# RT_SUPER_B1.net
KiCad netlist of a schematic drawn in Altium Designer
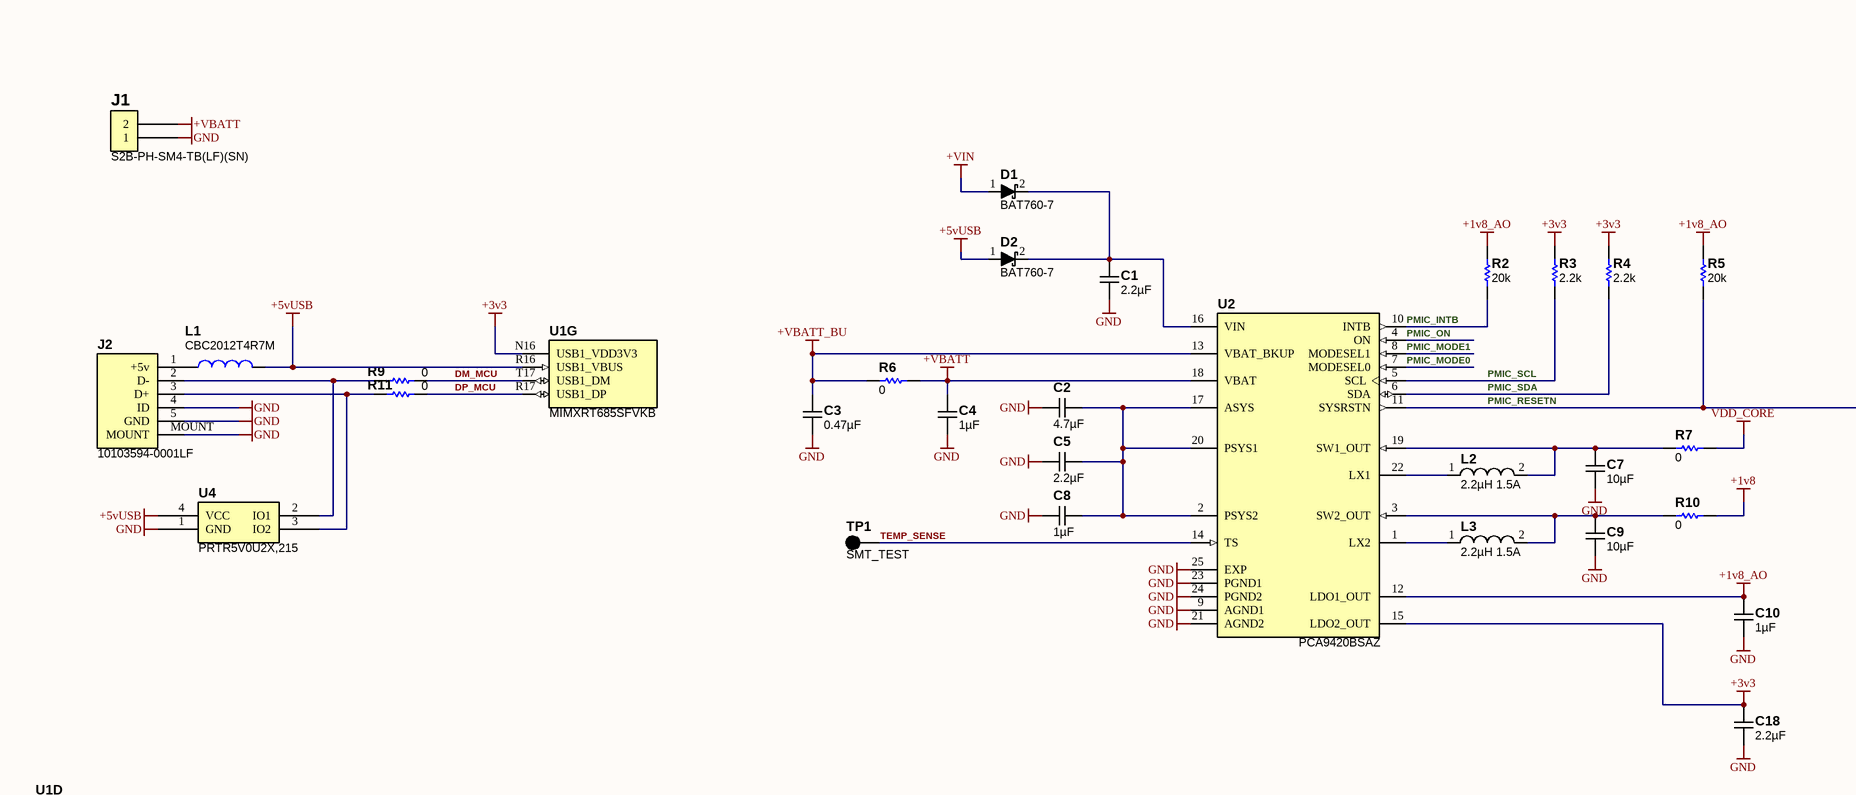
[diagram p0: RT_SUPER_B1.SchDoc, top left]
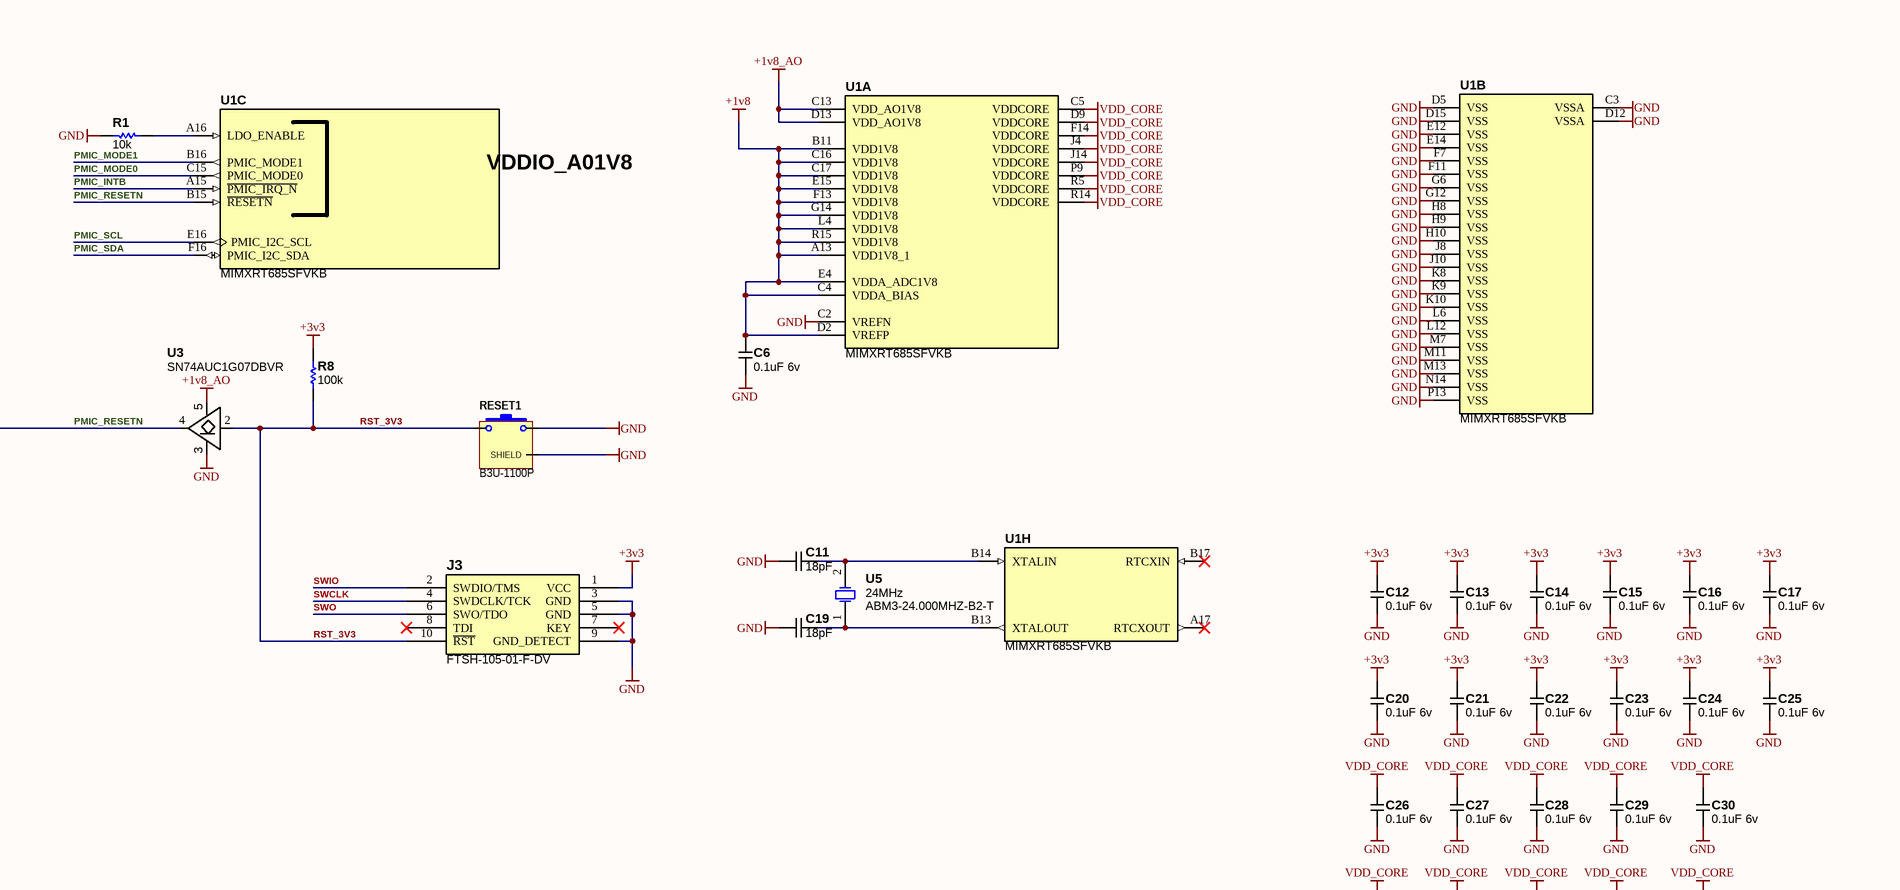
[diagram p1: RT_SUPER_B1.SchDoc, top right]
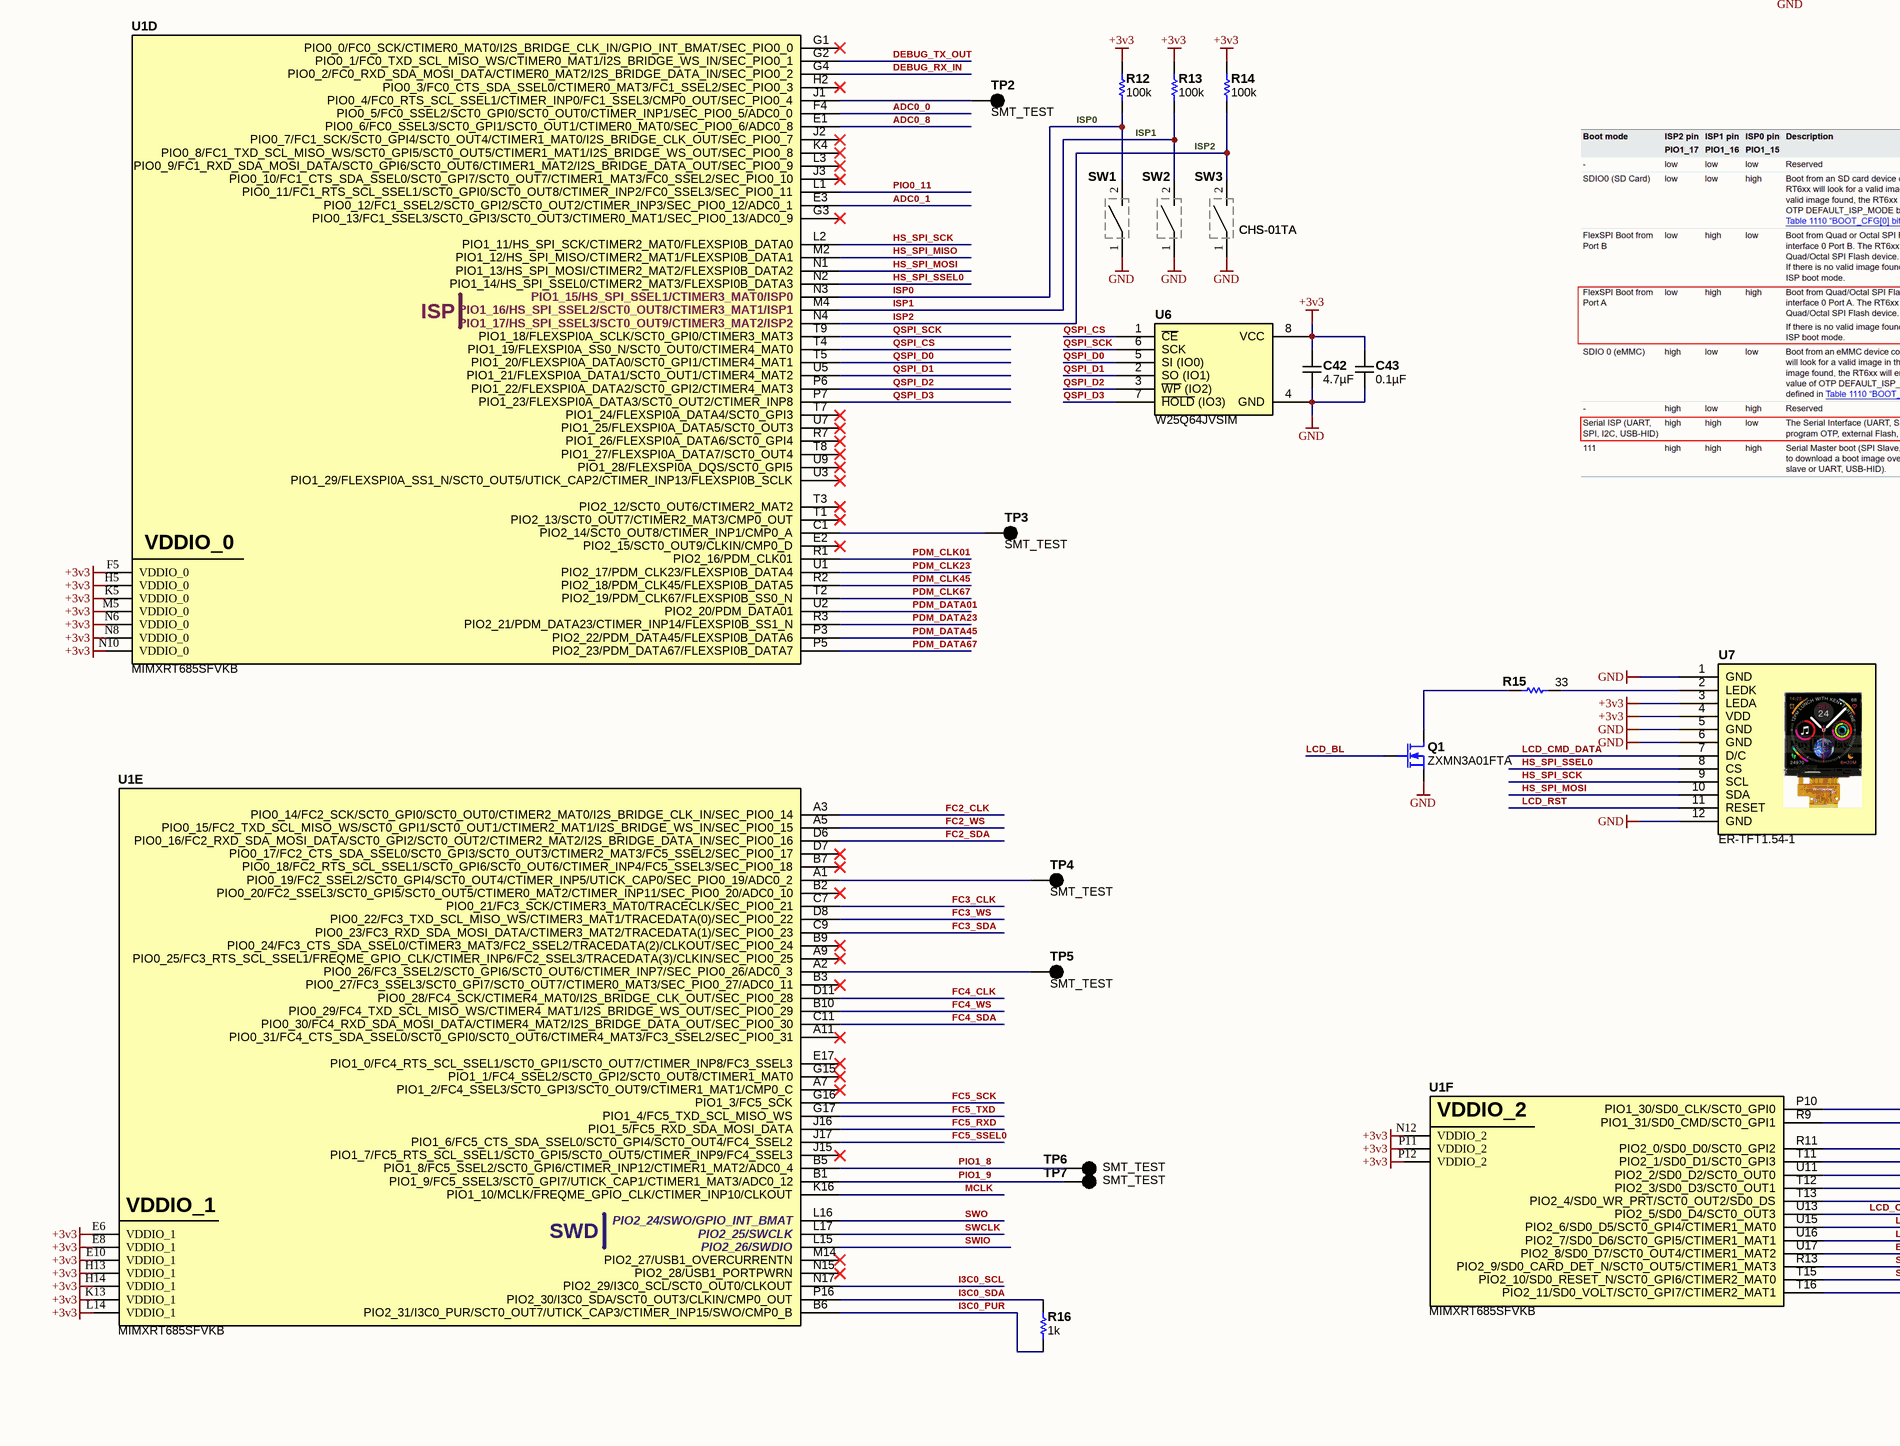
[diagram p2: RT_SUPER_B1.SchDoc, bottom left]
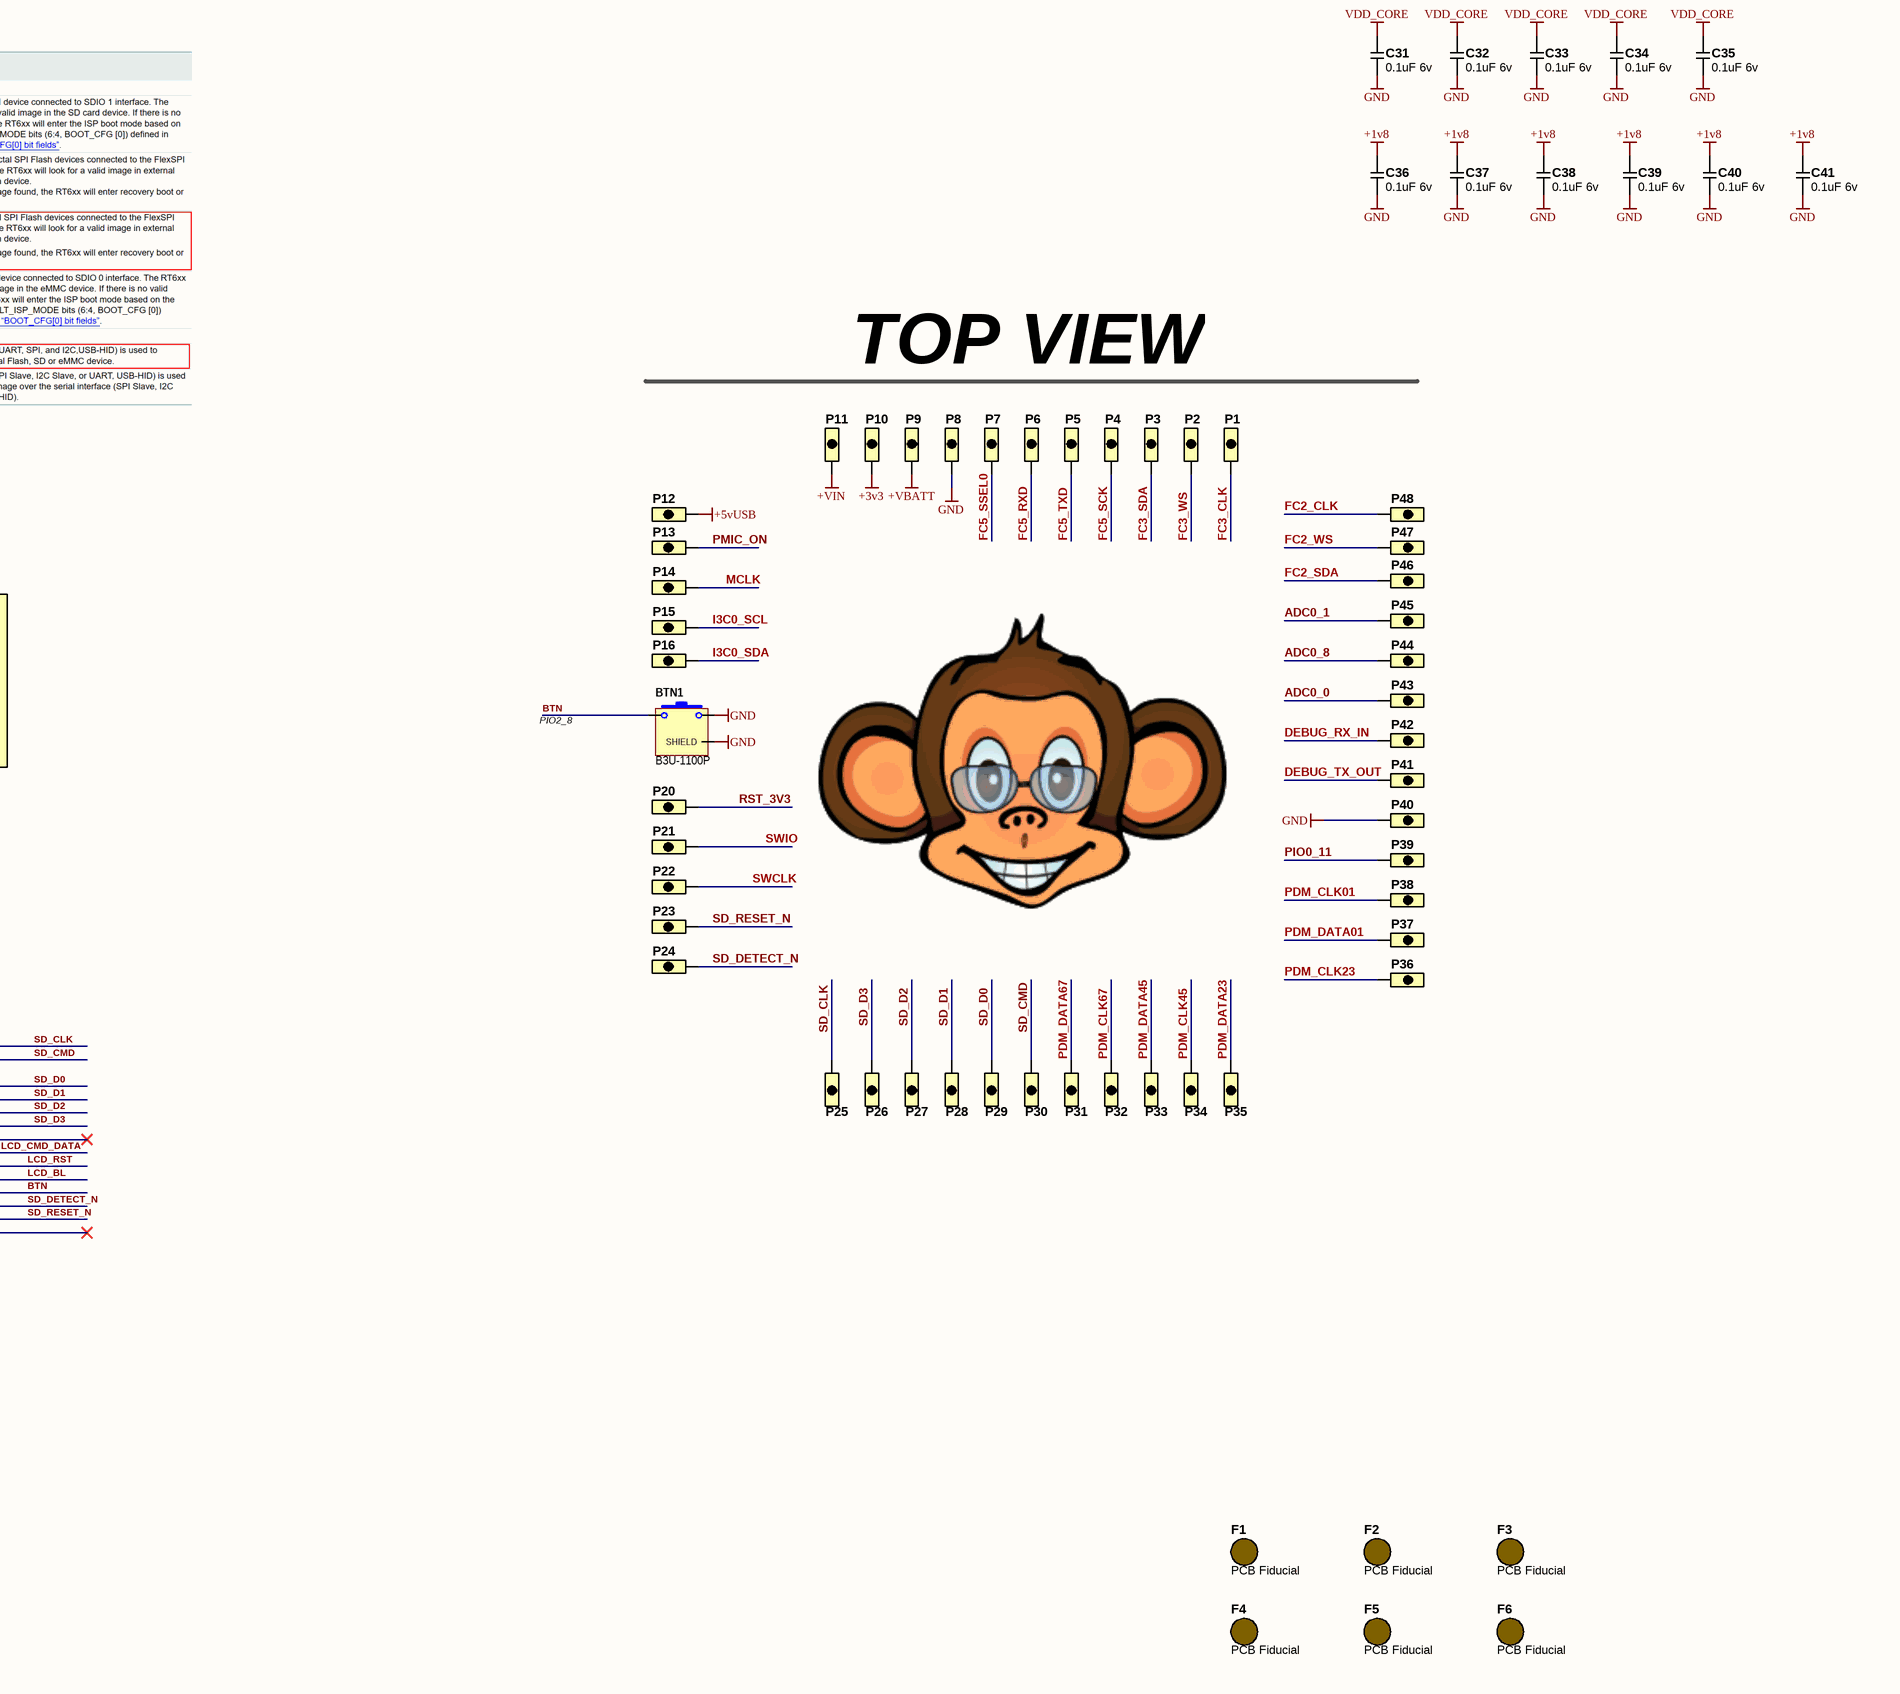
[diagram p3: RT_SUPER_B1.SchDoc, bottom right]

(export (version "E")
  (design (tool "Eeschema 10.0.6"))
  (components
    (comp (ref "BTN1")
      (value "B3U-1100P")
      (footprint "OMRON_B3U-1100P")
      (description "SWITCH TACTILE SPST-NO 0.05A 12V")
      (fields (field (name "MANUFACTURER") "Omron Electronics Inc-EMC Div"))
      (libsource (lib "Switches-N") (part "B3U-1100P"))
    )
    (comp (ref "C1")
      (value "2.2µF")
      (footprint "C0603_0.90MM_MD")
      (description "CAP CER 2.2UF 6.3V X7R 0603")
      (fields
        (field (name "MANUFACTURER PART NUMBER") "GCM188R70J225KE22D")
        (field (name "MANUFACTURER") "Murata Electronics")
      )
      (libsource (lib "Capacitors - Murata - AEC-Q200") (part "C_2P_NP"))
    )
    (comp (ref "C2")
      (value "4.7µF")
      (footprint "C0603_1.00MM_MD")
      (description "CAP CER 4.7UF 6.3V X7S 0603")
      (fields
        (field (name "MANUFACTURER PART NUMBER") "GCJ188C70J475KE02D")
        (field (name "MANUFACTURER") "Murata Electronics")
      )
      (libsource (lib "Capacitors - Murata - AEC-Q200") (part "C_2P_NP"))
    )
    (comp (ref "C3")
      (value "0.47µF")
      (footprint "C0402_0.55MM_HD")
      (description "CAP CER 0.47UF 25V X5R 0402")
      (fields
        (field (name "MANUFACTURER PART NUMBER") "GRT155R61E474KE01D")
        (field (name "MANUFACTURER") "Murata Electronics")
      )
      (libsource (lib "Capacitors - Murata - AEC-Q200") (part "C_2P_NP"))
    )
    (comp (ref "C4")
      (value "1µF")
      (footprint "C0402_0.55MM_HD")
      (description "CAP CER 1UF 10V X7S 0402")
      (fields
        (field (name "MANUFACTURER PART NUMBER") "GCM155C71A105KE38D")
        (field (name "MANUFACTURER") "Murata Electronics")
      )
      (libsource (lib "Capacitors - Murata - AEC-Q200") (part "C_2P_NP"))
    )
    (comp (ref "C5")
      (value "2.2µF")
      (footprint "C0603_0.90MM_MD")
      (description "CAP CER 2.2UF 6.3V X7R 0603")
      (fields
        (field (name "MANUFACTURER PART NUMBER") "GCM188R70J225KE22D")
        (field (name "MANUFACTURER") "Murata Electronics")
      )
      (libsource (lib "Capacitors - Murata - AEC-Q200") (part "C_2P_NP"))
    )
    (comp (ref "C6")
      (value "0.1uF 6v")
      (footprint "C0201_PERFECT")
      (description "Cap Ceramic 0.1uF 6.3VDC X5R 10% SMD 0201 Paper T/R")
      (fields
        (field (name "MANUFACTURER PART NUMBER") "CC0201KRX5R5BB104")
        (field (name "MANUFACTURER") "Yageo")
      )
      (libsource (lib "eCapacitors") (part "CC0201KRX5R5BB104"))
    )
    (comp (ref "C7")
      (value "10µF")
      (footprint "C0603_0.90MM_MD")
      (description "CAP CER 10UF 10V X5R 0603")
      (fields
        (field (name "MANUFACTURER PART NUMBER") "GRT188R61A106ME13D")
        (field (name "MANUFACTURER") "Murata Electronics")
      )
      (libsource (lib "Capacitors - Murata - AEC-Q200") (part "C_2P_NP"))
    )
    (comp (ref "C8")
      (value "1µF")
      (footprint "C0402_0.55MM_HD")
      (description "CAP CER 1UF 10V X7S 0402")
      (fields
        (field (name "MANUFACTURER PART NUMBER") "GCM155C71A105KE38D")
        (field (name "MANUFACTURER") "Murata Electronics")
      )
      (libsource (lib "Capacitors - Murata - AEC-Q200") (part "C_2P_NP"))
    )
    (comp (ref "C9")
      (value "10µF")
      (footprint "C0603_0.90MM_MD")
      (description "CAP CER 10UF 10V X5R 0603")
      (fields
        (field (name "MANUFACTURER PART NUMBER") "GRT188R61A106ME13D")
        (field (name "MANUFACTURER") "Murata Electronics")
      )
      (libsource (lib "Capacitors - Murata - AEC-Q200") (part "C_2P_NP"))
    )
    (comp (ref "C10")
      (value "1µF")
      (footprint "C0402_0.55MM_HD")
      (description "CAP CER 1UF 10V X7S 0402")
      (fields
        (field (name "MANUFACTURER PART NUMBER") "GCM155C71A105KE38D")
        (field (name "MANUFACTURER") "Murata Electronics")
      )
      (libsource (lib "Capacitors - Murata - AEC-Q200") (part "C_2P_NP"))
    )
    (comp (ref "C11")
      (value "18pF")
      (footprint "C0402_0.55MM_HD")
      (description "CAP CER 18PF 50V C0G 0402")
      (fields
        (field (name "MANUFACTURER PART NUMBER") "CGA2B2C0G1H180J050BA")
        (field (name "MANUFACTURER") "TDK Corporation")
      )
      (libsource (lib "Capacitors - TDK- AEC-Q200") (part "C_2P_NP"))
    )
    (comp (ref "C12")
      (value "0.1uF 6v")
      (footprint "C0201_PERFECT")
      (description "Cap Ceramic 0.1uF 6.3VDC X5R 10% SMD 0201 Paper T/R")
      (fields
        (field (name "MANUFACTURER PART NUMBER") "CC0201KRX5R5BB104")
        (field (name "MANUFACTURER") "Yageo")
      )
      (libsource (lib "eCapacitors") (part "CC0201KRX5R5BB104"))
    )
    (comp (ref "C13")
      (value "0.1uF 6v")
      (footprint "C0201_PERFECT")
      (description "Cap Ceramic 0.1uF 6.3VDC X5R 10% SMD 0201 Paper T/R")
      (fields
        (field (name "MANUFACTURER PART NUMBER") "CC0201KRX5R5BB104")
        (field (name "MANUFACTURER") "Yageo")
      )
      (libsource (lib "eCapacitors") (part "CC0201KRX5R5BB104"))
    )
    (comp (ref "C14")
      (value "0.1uF 6v")
      (footprint "C0201_PERFECT")
      (description "Cap Ceramic 0.1uF 6.3VDC X5R 10% SMD 0201 Paper T/R")
      (fields
        (field (name "MANUFACTURER PART NUMBER") "CC0201KRX5R5BB104")
        (field (name "MANUFACTURER") "Yageo")
      )
      (libsource (lib "eCapacitors") (part "CC0201KRX5R5BB104"))
    )
    (comp (ref "C15")
      (value "0.1uF 6v")
      (footprint "C0201_PERFECT")
      (description "Cap Ceramic 0.1uF 6.3VDC X5R 10% SMD 0201 Paper T/R")
      (fields
        (field (name "MANUFACTURER PART NUMBER") "CC0201KRX5R5BB104")
        (field (name "MANUFACTURER") "Yageo")
      )
      (libsource (lib "eCapacitors") (part "CC0201KRX5R5BB104"))
    )
    (comp (ref "C16")
      (value "0.1uF 6v")
      (footprint "C0201_PERFECT")
      (description "Cap Ceramic 0.1uF 6.3VDC X5R 10% SMD 0201 Paper T/R")
      (fields
        (field (name "MANUFACTURER PART NUMBER") "CC0201KRX5R5BB104")
        (field (name "MANUFACTURER") "Yageo")
      )
      (libsource (lib "eCapacitors") (part "CC0201KRX5R5BB104"))
    )
    (comp (ref "C17")
      (value "0.1uF 6v")
      (footprint "C0201_PERFECT")
      (description "Cap Ceramic 0.1uF 6.3VDC X5R 10% SMD 0201 Paper T/R")
      (fields
        (field (name "MANUFACTURER PART NUMBER") "CC0201KRX5R5BB104")
        (field (name "MANUFACTURER") "Yageo")
      )
      (libsource (lib "eCapacitors") (part "CC0201KRX5R5BB104"))
    )
    (comp (ref "C18")
      (value "2.2µF")
      (footprint "C0603_0.90MM_MD")
      (description "CAP CER 2.2UF 6.3V X7R 0603")
      (fields
        (field (name "MANUFACTURER PART NUMBER") "GCM188R70J225KE22D")
        (field (name "MANUFACTURER") "Murata Electronics")
      )
      (libsource (lib "Capacitors - Murata - AEC-Q200") (part "C_2P_NP"))
    )
    (comp (ref "C19")
      (value "18pF")
      (footprint "C0402_0.55MM_HD")
      (description "CAP CER 18PF 50V C0G 0402")
      (fields
        (field (name "MANUFACTURER PART NUMBER") "CGA2B2C0G1H180J050BA")
        (field (name "MANUFACTURER") "TDK Corporation")
      )
      (libsource (lib "Capacitors - TDK- AEC-Q200") (part "C_2P_NP"))
    )
    (comp (ref "C20")
      (value "0.1uF 6v")
      (footprint "C0201_PERFECT")
      (description "Cap Ceramic 0.1uF 6.3VDC X5R 10% SMD 0201 Paper T/R")
      (fields
        (field (name "MANUFACTURER PART NUMBER") "CC0201KRX5R5BB104")
        (field (name "MANUFACTURER") "Yageo")
      )
      (libsource (lib "eCapacitors") (part "CC0201KRX5R5BB104"))
    )
    (comp (ref "C21")
      (value "0.1uF 6v")
      (footprint "C0201_PERFECT")
      (description "Cap Ceramic 0.1uF 6.3VDC X5R 10% SMD 0201 Paper T/R")
      (fields
        (field (name "MANUFACTURER PART NUMBER") "CC0201KRX5R5BB104")
        (field (name "MANUFACTURER") "Yageo")
      )
      (libsource (lib "eCapacitors") (part "CC0201KRX5R5BB104"))
    )
    (comp (ref "C22")
      (value "0.1uF 6v")
      (footprint "C0201_PERFECT")
      (description "Cap Ceramic 0.1uF 6.3VDC X5R 10% SMD 0201 Paper T/R")
      (fields
        (field (name "MANUFACTURER PART NUMBER") "CC0201KRX5R5BB104")
        (field (name "MANUFACTURER") "Yageo")
      )
      (libsource (lib "eCapacitors") (part "CC0201KRX5R5BB104"))
    )
    (comp (ref "C23")
      (value "0.1uF 6v")
      (footprint "C0201_PERFECT")
      (description "Cap Ceramic 0.1uF 6.3VDC X5R 10% SMD 0201 Paper T/R")
      (fields
        (field (name "MANUFACTURER PART NUMBER") "CC0201KRX5R5BB104")
        (field (name "MANUFACTURER") "Yageo")
      )
      (libsource (lib "eCapacitors") (part "CC0201KRX5R5BB104"))
    )
    (comp (ref "C24")
      (value "0.1uF 6v")
      (footprint "C0201_PERFECT")
      (description "Cap Ceramic 0.1uF 6.3VDC X5R 10% SMD 0201 Paper T/R")
      (fields
        (field (name "MANUFACTURER PART NUMBER") "CC0201KRX5R5BB104")
        (field (name "MANUFACTURER") "Yageo")
      )
      (libsource (lib "eCapacitors") (part "CC0201KRX5R5BB104"))
    )
    (comp (ref "C25")
      (value "0.1uF 6v")
      (footprint "C0201_PERFECT")
      (description "Cap Ceramic 0.1uF 6.3VDC X5R 10% SMD 0201 Paper T/R")
      (fields
        (field (name "MANUFACTURER PART NUMBER") "CC0201KRX5R5BB104")
        (field (name "MANUFACTURER") "Yageo")
      )
      (libsource (lib "eCapacitors") (part "CC0201KRX5R5BB104"))
    )
    (comp (ref "C26")
      (value "0.1uF 6v")
      (footprint "C0201_PERFECT")
      (description "Cap Ceramic 0.1uF 6.3VDC X5R 10% SMD 0201 Paper T/R")
      (fields
        (field (name "MANUFACTURER PART NUMBER") "CC0201KRX5R5BB104")
        (field (name "MANUFACTURER") "Yageo")
      )
      (libsource (lib "eCapacitors") (part "CC0201KRX5R5BB104"))
    )
    (comp (ref "C27")
      (value "0.1uF 6v")
      (footprint "C0201_PERFECT")
      (description "Cap Ceramic 0.1uF 6.3VDC X5R 10% SMD 0201 Paper T/R")
      (fields
        (field (name "MANUFACTURER PART NUMBER") "CC0201KRX5R5BB104")
        (field (name "MANUFACTURER") "Yageo")
      )
      (libsource (lib "eCapacitors") (part "CC0201KRX5R5BB104"))
    )
    (comp (ref "C28")
      (value "0.1uF 6v")
      (footprint "C0201_PERFECT")
      (description "Cap Ceramic 0.1uF 6.3VDC X5R 10% SMD 0201 Paper T/R")
      (fields
        (field (name "MANUFACTURER PART NUMBER") "CC0201KRX5R5BB104")
        (field (name "MANUFACTURER") "Yageo")
      )
      (libsource (lib "eCapacitors") (part "CC0201KRX5R5BB104"))
    )
    (comp (ref "C29")
      (value "0.1uF 6v")
      (footprint "C0201_PERFECT")
      (description "Cap Ceramic 0.1uF 6.3VDC X5R 10% SMD 0201 Paper T/R")
      (fields
        (field (name "MANUFACTURER PART NUMBER") "CC0201KRX5R5BB104")
        (field (name "MANUFACTURER") "Yageo")
      )
      (libsource (lib "eCapacitors") (part "CC0201KRX5R5BB104"))
    )
    (comp (ref "C30")
      (value "0.1uF 6v")
      (footprint "C0201_PERFECT")
      (description "Cap Ceramic 0.1uF 6.3VDC X5R 10% SMD 0201 Paper T/R")
      (fields
        (field (name "MANUFACTURER PART NUMBER") "CC0201KRX5R5BB104")
        (field (name "MANUFACTURER") "Yageo")
      )
      (libsource (lib "eCapacitors") (part "CC0201KRX5R5BB104"))
    )
    (comp (ref "C31")
      (value "0.1uF 6v")
      (footprint "C0201_PERFECT")
      (description "Cap Ceramic 0.1uF 6.3VDC X5R 10% SMD 0201 Paper T/R")
      (fields
        (field (name "MANUFACTURER PART NUMBER") "CC0201KRX5R5BB104")
        (field (name "MANUFACTURER") "Yageo")
      )
      (libsource (lib "eCapacitors") (part "CC0201KRX5R5BB104"))
    )
    (comp (ref "C32")
      (value "0.1uF 6v")
      (footprint "C0201_PERFECT")
      (description "Cap Ceramic 0.1uF 6.3VDC X5R 10% SMD 0201 Paper T/R")
      (fields
        (field (name "MANUFACTURER PART NUMBER") "CC0201KRX5R5BB104")
        (field (name "MANUFACTURER") "Yageo")
      )
      (libsource (lib "eCapacitors") (part "CC0201KRX5R5BB104"))
    )
    (comp (ref "C33")
      (value "0.1uF 6v")
      (footprint "C0201_PERFECT")
      (description "Cap Ceramic 0.1uF 6.3VDC X5R 10% SMD 0201 Paper T/R")
      (fields
        (field (name "MANUFACTURER PART NUMBER") "CC0201KRX5R5BB104")
        (field (name "MANUFACTURER") "Yageo")
      )
      (libsource (lib "eCapacitors") (part "CC0201KRX5R5BB104"))
    )
    (comp (ref "C34")
      (value "0.1uF 6v")
      (footprint "C0201_PERFECT")
      (description "Cap Ceramic 0.1uF 6.3VDC X5R 10% SMD 0201 Paper T/R")
      (fields
        (field (name "MANUFACTURER PART NUMBER") "CC0201KRX5R5BB104")
        (field (name "MANUFACTURER") "Yageo")
      )
      (libsource (lib "eCapacitors") (part "CC0201KRX5R5BB104"))
    )
    (comp (ref "C35")
      (value "0.1uF 6v")
      (footprint "C0201_PERFECT")
      (description "Cap Ceramic 0.1uF 6.3VDC X5R 10% SMD 0201 Paper T/R")
      (fields
        (field (name "MANUFACTURER PART NUMBER") "CC0201KRX5R5BB104")
        (field (name "MANUFACTURER") "Yageo")
      )
      (libsource (lib "eCapacitors") (part "CC0201KRX5R5BB104"))
    )
    (comp (ref "C36")
      (value "0.1uF 6v")
      (footprint "C0201_PERFECT")
      (description "Cap Ceramic 0.1uF 6.3VDC X5R 10% SMD 0201 Paper T/R")
      (fields
        (field (name "MANUFACTURER PART NUMBER") "CC0201KRX5R5BB104")
        (field (name "MANUFACTURER") "Yageo")
      )
      (libsource (lib "eCapacitors") (part "CC0201KRX5R5BB104"))
    )
    (comp (ref "C37")
      (value "0.1uF 6v")
      (footprint "C0201_PERFECT")
      (description "Cap Ceramic 0.1uF 6.3VDC X5R 10% SMD 0201 Paper T/R")
      (fields
        (field (name "MANUFACTURER PART NUMBER") "CC0201KRX5R5BB104")
        (field (name "MANUFACTURER") "Yageo")
      )
      (libsource (lib "eCapacitors") (part "CC0201KRX5R5BB104"))
    )
    (comp (ref "C38")
      (value "0.1uF 6v")
      (footprint "C0201_PERFECT")
      (description "Cap Ceramic 0.1uF 6.3VDC X5R 10% SMD 0201 Paper T/R")
      (fields
        (field (name "MANUFACTURER PART NUMBER") "CC0201KRX5R5BB104")
        (field (name "MANUFACTURER") "Yageo")
      )
      (libsource (lib "eCapacitors") (part "CC0201KRX5R5BB104"))
    )
    (comp (ref "C39")
      (value "0.1uF 6v")
      (footprint "C0201_PERFECT")
      (description "Cap Ceramic 0.1uF 6.3VDC X5R 10% SMD 0201 Paper T/R")
      (fields
        (field (name "MANUFACTURER PART NUMBER") "CC0201KRX5R5BB104")
        (field (name "MANUFACTURER") "Yageo")
      )
      (libsource (lib "eCapacitors") (part "CC0201KRX5R5BB104"))
    )
    (comp (ref "C40")
      (value "0.1uF 6v")
      (footprint "C0201_PERFECT")
      (description "Cap Ceramic 0.1uF 6.3VDC X5R 10% SMD 0201 Paper T/R")
      (fields
        (field (name "MANUFACTURER PART NUMBER") "CC0201KRX5R5BB104")
        (field (name "MANUFACTURER") "Yageo")
      )
      (libsource (lib "eCapacitors") (part "CC0201KRX5R5BB104"))
    )
    (comp (ref "C41")
      (value "0.1uF 6v")
      (footprint "C0201_PERFECT")
      (description "Cap Ceramic 0.1uF 6.3VDC X5R 10% SMD 0201 Paper T/R")
      (fields
        (field (name "MANUFACTURER PART NUMBER") "CC0201KRX5R5BB104")
        (field (name "MANUFACTURER") "Yageo")
      )
      (libsource (lib "eCapacitors") (part "CC0201KRX5R5BB104"))
    )
    (comp (ref "C42")
      (value "4.7µF")
      (footprint "C0805_1.45MM_MD")
      (description "CAP CER 4.7UF 10V X7R 0805")
      (fields
        (field (name "MANUFACTURER PART NUMBER") "CGA4J3X7R1A475K125AB")
        (field (name "MANUFACTURER") "TDK Corporation")
      )
      (libsource (lib "Capacitors - TDK- AEC-Q200") (part "C_2P_NP"))
    )
    (comp (ref "C43")
      (value "0.1µF")
      (footprint "C0402_0.55MM_MD")
      (description "CAP CER 0.1UF 16V X7R 0402")
      (fields
        (field (name "MANUFACTURER PART NUMBER") "CGA2B1X7R1C104K050BC")
        (field (name "MANUFACTURER") "TDK Corporation")
      )
      (libsource (lib "Capacitors - TDK- AEC-Q200") (part "C_2P_NP"))
    )
    (comp (ref "D1")
      (value "BAT760-7")
      (footprint "D_SOD-323_P")
      (description "DIODE SCHOTTKY 30V 1A SOD323")
      (fields (field (name "MANUFACTURER") "Diodes Inc"))
      (libsource (lib "Diodes") (part "DS_1A_2C"))
    )
    (comp (ref "D2")
      (value "BAT760-7")
      (footprint "D_SOD-323_P")
      (description "DIODE SCHOTTKY 30V 1A SOD323")
      (fields (field (name "MANUFACTURER") "Diodes Inc"))
      (libsource (lib "Diodes") (part "DS_1A_2C"))
    )
    (comp (ref "F1")
      (value "PCB Fiducial")
      (footprint "Fiducial 1mm - 2mm")
      (libsource (lib "eFiducial") (part "Fiducial"))
    )
    (comp (ref "F2")
      (value "PCB Fiducial")
      (footprint "Fiducial 1mm - 2mm")
      (libsource (lib "eFiducial") (part "Fiducial"))
    )
    (comp (ref "F3")
      (value "PCB Fiducial")
      (footprint "Fiducial 1mm - 2mm")
      (libsource (lib "eFiducial") (part "Fiducial"))
    )
    (comp (ref "F4")
      (value "PCB Fiducial")
      (footprint "Fiducial 1mm - 2mm")
      (libsource (lib "eFiducial") (part "Fiducial"))
    )
    (comp (ref "F5")
      (value "PCB Fiducial")
      (footprint "Fiducial 1mm - 2mm")
      (libsource (lib "eFiducial") (part "Fiducial"))
    )
    (comp (ref "F6")
      (value "PCB Fiducial")
      (footprint "Fiducial 1mm - 2mm")
      (libsource (lib "eFiducial") (part "Fiducial"))
    )
    (comp (ref "J1")
      (value "S2B-PH-SM4-TB(LF)(SN)")
      (footprint "S2B-PH-SM4-TB(LF)(SN)")
      (description "CONN HEADER PH SIDE 2POS 2MM SMD")
      (fields (field (name "MANUFACTURER") "JST Sales America Inc"))
      (libsource (lib "eConnector_JST_PH") (part "S2B-PH-SM4-TB(LF)(SN)"))
    )
    (comp (ref "J2")
      (value "10103594-0001LF")
      (footprint "10103594-0001LF")
      (description "CONN RCPT STD MICRO USB TYPE B")
      (fields (field (name "MANUFACTURER") "FCI"))
      (libsource (lib "eConnector_USB") (part "10103594-0001LF"))
    )
    (comp (ref "J3")
      (value "FTSH-105-01-F-DV")
      (footprint "FTSH-105-01-F-DV-K-A")
      (description "SAMTEC - FTSH-105-01-F-DV - .050 X .050")
      (fields (field (name "MANUFACTURER") "SAMTEC"))
      (libsource (lib "eConnector") (part "CORTEX-DEBUG"))
    )
    (comp (ref "L1")
      (value "CBC2012T4R7M")
      (footprint "C0805_1.45MM_MD")
      (description "FIXED IND 4.7UH 520MA 650 MOHM")
      (fields (field (name "MANUFACTURER") "Taiyo Yuden") (field (name "TOLERANCE") "20%"))
      (libsource (lib "eInductor") (part "CBC2012T4R7M"))
    )
    (comp (ref "L2")
      (value "2.2µH 1.5A")
      (footprint "L_NRH3012")
      (description "Inductor 2.2µH 1.5A")
      (fields
        (field (name "MANUFACTURER PART NUMBER") "NRH3012T2R2MN")
        (field (name "MANUFACTURER") "Taiyo Yuden")
      )
      (libsource (lib "Inductors") (part "L_2P"))
    )
    (comp (ref "L3")
      (value "2.2µH 1.5A")
      (footprint "L_NRH3012")
      (description "Inductor 2.2µH 1.5A")
      (fields
        (field (name "MANUFACTURER PART NUMBER") "NRH3012T2R2MN")
        (field (name "MANUFACTURER") "Taiyo Yuden")
      )
      (libsource (lib "Inductors") (part "L_2P"))
    )
    (comp (ref "P1")
      (value "~")
      (footprint "CASTELLATED")
      (libsource (lib "eConnector") (part "CASTELLATED"))
    )
    (comp (ref "P2")
      (value "~")
      (footprint "CASTELLATED")
      (libsource (lib "eConnector") (part "CASTELLATED"))
    )
    (comp (ref "P3")
      (value "~")
      (footprint "CASTELLATED")
      (libsource (lib "eConnector") (part "CASTELLATED"))
    )
    (comp (ref "P4")
      (value "~")
      (footprint "CASTELLATED")
      (libsource (lib "eConnector") (part "CASTELLATED"))
    )
    (comp (ref "P5")
      (value "~")
      (footprint "CASTELLATED")
      (libsource (lib "eConnector") (part "CASTELLATED"))
    )
    (comp (ref "P6")
      (value "~")
      (footprint "CASTELLATED")
      (libsource (lib "eConnector") (part "CASTELLATED"))
    )
    (comp (ref "P7")
      (value "~")
      (footprint "CASTELLATED")
      (libsource (lib "eConnector") (part "CASTELLATED"))
    )
    (comp (ref "P8")
      (value "~")
      (footprint "CASTELLATED")
      (libsource (lib "eConnector") (part "CASTELLATED"))
    )
    (comp (ref "P9")
      (value "~")
      (footprint "CASTELLATED")
      (libsource (lib "eConnector") (part "CASTELLATED"))
    )
    (comp (ref "P10")
      (value "~")
      (footprint "CASTELLATED")
      (libsource (lib "eConnector") (part "CASTELLATED"))
    )
    (comp (ref "P11")
      (value "~")
      (footprint "CASTELLATED")
      (libsource (lib "eConnector") (part "CASTELLATED"))
    )
    (comp (ref "P12") (value "~") (footprint "CASTELLATED") (libsource (lib "") (part "CASTELLATED_1")))
    (comp (ref "P13") (value "~") (footprint "CASTELLATED") (libsource (lib "") (part "CASTELLATED_2")))
    (comp (ref "P14") (value "~") (footprint "CASTELLATED") (libsource (lib "") (part "CASTELLATED_2")))
    (comp (ref "P15") (value "~") (footprint "CASTELLATED") (libsource (lib "") (part "CASTELLATED_2")))
    (comp (ref "P16") (value "~") (footprint "CASTELLATED") (libsource (lib "") (part "CASTELLATED_2")))
    (comp (ref "P20") (value "~") (footprint "CASTELLATED") (libsource (lib "") (part "CASTELLATED_2")))
    (comp (ref "P21") (value "~") (footprint "CASTELLATED") (libsource (lib "") (part "CASTELLATED_2")))
    (comp (ref "P22") (value "~") (footprint "CASTELLATED") (libsource (lib "") (part "CASTELLATED_2")))
    (comp (ref "P23") (value "~") (footprint "CASTELLATED") (libsource (lib "") (part "CASTELLATED_2")))
    (comp (ref "P24") (value "~") (footprint "CASTELLATED") (libsource (lib "") (part "CASTELLATED_1")))
    (comp (ref "P25") (value "~") (footprint "CASTELLATED") (libsource (lib "") (part "CASTELLATED_1")))
    (comp (ref "P26") (value "~") (footprint "CASTELLATED") (libsource (lib "") (part "CASTELLATED_1")))
    (comp (ref "P27") (value "~") (footprint "CASTELLATED") (libsource (lib "") (part "CASTELLATED_1")))
    (comp (ref "P28") (value "~") (footprint "CASTELLATED") (libsource (lib "") (part "CASTELLATED_1")))
    (comp (ref "P29") (value "~") (footprint "CASTELLATED") (libsource (lib "") (part "CASTELLATED_1")))
    (comp (ref "P30") (value "~") (footprint "CASTELLATED") (libsource (lib "") (part "CASTELLATED_1")))
    (comp (ref "P31") (value "~") (footprint "CASTELLATED") (libsource (lib "") (part "CASTELLATED_1")))
    (comp (ref "P32") (value "~") (footprint "CASTELLATED") (libsource (lib "") (part "CASTELLATED_1")))
    (comp (ref "P33") (value "~") (footprint "CASTELLATED") (libsource (lib "") (part "CASTELLATED_1")))
    (comp (ref "P34") (value "~") (footprint "CASTELLATED") (libsource (lib "") (part "CASTELLATED_1")))
    (comp (ref "P35") (value "~") (footprint "CASTELLATED") (libsource (lib "") (part "CASTELLATED_1")))
    (comp (ref "P36")
      (value "~")
      (footprint "CASTELLATED")
      (libsource (lib "eConnector") (part "CASTELLATED"))
    )
    (comp (ref "P37")
      (value "~")
      (footprint "CASTELLATED")
      (libsource (lib "eConnector") (part "CASTELLATED"))
    )
    (comp (ref "P38")
      (value "~")
      (footprint "CASTELLATED")
      (libsource (lib "eConnector") (part "CASTELLATED"))
    )
    (comp (ref "P39")
      (value "~")
      (footprint "CASTELLATED")
      (libsource (lib "eConnector") (part "CASTELLATED"))
    )
    (comp (ref "P40")
      (value "~")
      (footprint "CASTELLATED")
      (libsource (lib "eConnector") (part "CASTELLATED"))
    )
    (comp (ref "P41")
      (value "~")
      (footprint "CASTELLATED")
      (libsource (lib "eConnector") (part "CASTELLATED"))
    )
    (comp (ref "P42")
      (value "~")
      (footprint "CASTELLATED")
      (libsource (lib "eConnector") (part "CASTELLATED"))
    )
    (comp (ref "P43")
      (value "~")
      (footprint "CASTELLATED")
      (libsource (lib "eConnector") (part "CASTELLATED"))
    )
    (comp (ref "P44")
      (value "~")
      (footprint "CASTELLATED")
      (libsource (lib "eConnector") (part "CASTELLATED"))
    )
    (comp (ref "P45")
      (value "~")
      (footprint "CASTELLATED")
      (libsource (lib "eConnector") (part "CASTELLATED"))
    )
    (comp (ref "P46")
      (value "~")
      (footprint "CASTELLATED")
      (libsource (lib "eConnector") (part "CASTELLATED"))
    )
    (comp (ref "P47")
      (value "~")
      (footprint "CASTELLATED")
      (libsource (lib "eConnector") (part "CASTELLATED"))
    )
    (comp (ref "P48")
      (value "~")
      (footprint "CASTELLATED")
      (libsource (lib "eConnector") (part "CASTELLATED"))
    )
    (comp (ref "Q1")
      (value "ZXMN3A01FTA")
      (footprint "SOT-23")
      (description "MOSFET N-CH 30V 1.8A SOT23-3")
      (fields (field (name "MANUFACTURER") "Diodes/Zetex"))
      (libsource (lib "eTransistor") (part "ZXMN3A01FTA"))
    )
    (comp (ref "R1")
      (value "10k")
      (footprint "R0402_0.40MM_HD")
      (description "RES 10K OHM 1/10W 1% 0402 SMD")
      (fields
        (field (name "MANUFACTURER PART NUMBER") "ERJ-2RKF1002X")
        (field (name "MANUFACTURER") "Panasonic Electronic Components")
      )
      (libsource (lib "Resistors - Panasonic - AEC-Q200") (part "R_2P"))
    )
    (comp (ref "R2")
      (value "20k")
      (footprint "R0402_0.40MM_HD")
      (description "RES 20K OHM 1/10W 1% 0402 SMD")
      (fields
        (field (name "MANUFACTURER PART NUMBER") "ERJ-2RKF2002X")
        (field (name "MANUFACTURER") "Panasonic Electronic Components")
      )
      (libsource (lib "Resistors - Panasonic - AEC-Q200") (part "R_2P"))
    )
    (comp (ref "R3")
      (value "2.2k")
      (footprint "R0402_0.40MM_HD")
      (description "RES 2.2K OHM 1/10W 1% 0402 SMD")
      (fields
        (field (name "MANUFACTURER PART NUMBER") "ERJ-2RKF2201X")
        (field (name "MANUFACTURER") "Panasonic Electronic Components")
      )
      (libsource (lib "Resistors - Panasonic - AEC-Q200") (part "R_2P"))
    )
    (comp (ref "R4")
      (value "2.2k")
      (footprint "R0402_0.40MM_HD")
      (description "RES 2.2K OHM 1/10W 1% 0402 SMD")
      (fields
        (field (name "MANUFACTURER PART NUMBER") "ERJ-2RKF2201X")
        (field (name "MANUFACTURER") "Panasonic Electronic Components")
      )
      (libsource (lib "Resistors - Panasonic - AEC-Q200") (part "R_2P"))
    )
    (comp (ref "R5")
      (value "20k")
      (footprint "R0402_0.40MM_HD")
      (description "RES 20K OHM 1/10W 1% 0402 SMD")
      (fields
        (field (name "MANUFACTURER PART NUMBER") "ERJ-2RKF2002X")
        (field (name "MANUFACTURER") "Panasonic Electronic Components")
      )
      (libsource (lib "Resistors - Panasonic - AEC-Q200") (part "R_2P"))
    )
    (comp (ref "R6")
      (value "0")
      (footprint "R0402_0.40MM_HD")
      (description "RES 0.0 OHM 1/10W JUMP 0402 SMD")
      (fields
        (field (name "MANUFACTURER PART NUMBER") "ERJ-2GE0R00X")
        (field (name "MANUFACTURER") "Panasonic Electronic Components")
      )
      (libsource (lib "Resistors - Panasonic - AEC-Q200") (part "R_2P"))
    )
    (comp (ref "R7")
      (value "0")
      (footprint "R0402_0.40MM_HD")
      (description "RES 0.0 OHM 1/10W JUMP 0402 SMD")
      (fields
        (field (name "MANUFACTURER PART NUMBER") "ERJ-2GE0R00X")
        (field (name "MANUFACTURER") "Panasonic Electronic Components")
      )
      (libsource (lib "Resistors - Panasonic - AEC-Q200") (part "R_2P"))
    )
    (comp (ref "R8")
      (value "100k")
      (footprint "R0402_0.40MM_HD")
      (description "RES 100K OHM 1/10W 1% 0402 SMD")
      (fields
        (field (name "MANUFACTURER PART NUMBER") "ERJ-2RKF1003X")
        (field (name "MANUFACTURER") "Panasonic Electronic Components")
      )
      (libsource (lib "Resistors - Panasonic - AEC-Q200") (part "R_2P"))
    )
    (comp (ref "R9")
      (value "0")
      (footprint "R0402_0.40MM_MD")
      (description "RES 0.0 OHM 1/10W JUMP 0402 SMD")
      (fields
        (field (name "MANUFACTURER PART NUMBER") "ERJ-2GE0R00X")
        (field (name "MANUFACTURER") "Panasonic Electronic Components")
      )
      (libsource (lib "Resistors - Panasonic - AEC-Q200") (part "R_2P"))
    )
    (comp (ref "R10")
      (value "0")
      (footprint "R0402_0.40MM_HD")
      (description "RES 0.0 OHM 1/10W JUMP 0402 SMD")
      (fields
        (field (name "MANUFACTURER PART NUMBER") "ERJ-2GE0R00X")
        (field (name "MANUFACTURER") "Panasonic Electronic Components")
      )
      (libsource (lib "Resistors - Panasonic - AEC-Q200") (part "R_2P"))
    )
    (comp (ref "R11")
      (value "0")
      (footprint "R0402_0.40MM_MD")
      (description "RES 0.0 OHM 1/10W JUMP 0402 SMD")
      (fields
        (field (name "MANUFACTURER PART NUMBER") "ERJ-2GE0R00X")
        (field (name "MANUFACTURER") "Panasonic Electronic Components")
      )
      (libsource (lib "Resistors - Panasonic - AEC-Q200") (part "R_2P"))
    )
    (comp (ref "R12")
      (value "100k")
      (footprint "R0402_0.40MM_HD")
      (description "RES 100K OHM 1/10W 1% 0402 SMD")
      (fields
        (field (name "MANUFACTURER PART NUMBER") "ERJ-2RKF1003X")
        (field (name "MANUFACTURER") "Panasonic Electronic Components")
      )
      (libsource (lib "Resistors - Panasonic - AEC-Q200") (part "R_2P"))
    )
    (comp (ref "R13")
      (value "100k")
      (footprint "R0402_0.40MM_HD")
      (description "RES 100K OHM 1/10W 1% 0402 SMD")
      (fields
        (field (name "MANUFACTURER PART NUMBER") "ERJ-2RKF1003X")
        (field (name "MANUFACTURER") "Panasonic Electronic Components")
      )
      (libsource (lib "Resistors - Panasonic - AEC-Q200") (part "R_2P"))
    )
    (comp (ref "R14")
      (value "100k")
      (footprint "R0402_0.40MM_HD")
      (description "RES 100K OHM 1/10W 1% 0402 SMD")
      (fields
        (field (name "MANUFACTURER PART NUMBER") "ERJ-2RKF1003X")
        (field (name "MANUFACTURER") "Panasonic Electronic Components")
      )
      (libsource (lib "Resistors - Panasonic - AEC-Q200") (part "R_2P"))
    )
    (comp (ref "R15")
      (value "33")
      (footprint "R0402_0.40MM_HD")
      (description "RES 33 OHM 1/10W 1% 0402 SMD")
      (fields
        (field (name "MANUFACTURER PART NUMBER") "ERJ-2RKF33R0X")
        (field (name "MANUFACTURER") "Panasonic Electronic Components")
      )
      (libsource (lib "Resistors - Panasonic - AEC-Q200") (part "R_2P"))
    )
    (comp (ref "R16")
      (value "1k")
      (footprint "R0402_0.40MM_HD")
      (description "RES 1K OHM 1/10W 1% 0402 SMD")
      (fields
        (field (name "MANUFACTURER PART NUMBER") "ERJ-2RKF1001X")
        (field (name "MANUFACTURER") "Panasonic Electronic Components")
      )
      (libsource (lib "Resistors - Panasonic - AEC-Q200") (part "R_2P"))
    )
    (comp (ref "RESET1")
      (value "B3U-1100P")
      (footprint "OMRON_B3U-1100P")
      (description "SWITCH TACTILE SPST-NO 0.05A 12V")
      (fields (field (name "MANUFACTURER") "Omron Electronics Inc-EMC Div"))
      (libsource (lib "Switches-N") (part "B3U-1100P"))
    )
    (comp (ref "SW1")
      (value "CHS-01TA")
      (footprint "CHS-01TA")
      (description "NIDEC COPAL ELECTRONICS - CHS-01TA - DIP SWITCH, 1POS, SPST, SLIDE, SMD")
      (fields (field (name "MANUFACTURER") "Nidec Copal"))
      (libsource (lib "eElectroMechanical") (part "CHS-01TA"))
    )
    (comp (ref "SW2")
      (value "CHS-01TA")
      (footprint "CHS-01TA")
      (description "NIDEC COPAL ELECTRONICS - CHS-01TA - DIP SWITCH, 1POS, SPST, SLIDE, SMD")
      (fields (field (name "MANUFACTURER") "Nidec Copal"))
      (libsource (lib "eElectroMechanical") (part "CHS-01TA"))
    )
    (comp (ref "SW3")
      (value "CHS-01TA")
      (footprint "CHS-01TA")
      (description "NIDEC COPAL ELECTRONICS - CHS-01TA - DIP SWITCH, 1POS, SPST, SLIDE, SMD")
      (fields (field (name "MANUFACTURER") "Nidec Copal"))
      (libsource (lib "eElectroMechanical") (part "CHS-01TA"))
    )
    (comp (ref "TP1")
      (value "SMT_TEST")
      (footprint "SMT_TP - 25 x 50")
      (libsource (lib "eTestPoint") (part "SMT_TEST"))
    )
    (comp (ref "TP2")
      (value "SMT_TEST")
      (footprint "SMT_TP - 35")
      (libsource (lib "eTestPoint") (part "SMT_TEST"))
    )
    (comp (ref "TP3")
      (value "SMT_TEST")
      (footprint "SMT_TP - 35")
      (libsource (lib "eTestPoint") (part "SMT_TEST"))
    )
    (comp (ref "TP4")
      (value "SMT_TEST")
      (footprint "SMT_TP - 35")
      (libsource (lib "eTestPoint") (part "SMT_TEST"))
    )
    (comp (ref "TP5")
      (value "SMT_TEST")
      (footprint "SMT_TP - 35")
      (libsource (lib "eTestPoint") (part "SMT_TEST"))
    )
    (comp (ref "TP6")
      (value "SMT_TEST")
      (footprint "SMT_TP - 35")
      (libsource (lib "eTestPoint") (part "SMT_TEST"))
    )
    (comp (ref "TP7")
      (value "SMT_TEST")
      (footprint "SMT_TP - 35")
      (libsource (lib "eTestPoint") (part "SMT_TEST"))
    )
    (comp (ref "U1")
      (value "MIMXRT685SFVKB")
      (footprint "VFBGA176")
      (description "SOC i.MX ARM Cortex M33 176-Pin VFBGA Tray")
      (fields (field (name "MANUFACTURER") "NXP Semiconductors"))
      (libsource (lib "eIC") (part "MIMXRT685SFVKB"))
    )
    (comp (ref "U2")
      (value "PCA9420BSAZ")
      (footprint "PCA9420")
      (description "Power Management IC for Low-Power Microcontroller Applications 24-Pin HVQFN")
      (fields (field (name "MANUFACTURER") "NXP Semiconductors"))
      (libsource (lib "eIC") (part "PCA9420BSAZ"))
    )
    (comp (ref "U3")
      (value "SN74AUC1G07DBVR")
      (footprint "SOT23-5")
      (description "IC BUFF NON-INVERT 2.7 V SOT23-5")
      (fields (field (name "MANUFACTURER") "Texas Instruments"))
      (libsource (lib "eIC") (part "SN74AUC1G07DBVR"))
    )
    (comp (ref "U4")
      (value "PRTR5V0U2X,215")
      (footprint "SOT143B")
      (description "TVS DIODE 5.5VWM SOT143B")
      (fields (field (name "MANUFACTURER") "NXP Semiconductors"))
      (libsource (lib "eDiode") (part "PRTR5V0U2X,215"))
    )
    (comp (ref "U5")
      (value "24MHz")
      (footprint "ABM3")
      (description "CRYSTAL 24.000MHZ 18PF SMD")
      (fields
        (field (name "MANUFACTURER") "Abracon Corporation")
        (field (name "MANUFACTURER PART NUMBER") "ABM3-24.000MHZ-B2-T")
      )
      (libsource (lib "eCrystal") (part "ABM3-24.000MHZ-B2-T"))
    )
    (comp (ref "U6")
      (value "W25Q64JVSIM")
      (footprint "SOIC127P830X200-8L")
      (description "NOR Flash Serial (SPI, Dual SPI, Quad SPI) 3V/3.3V 128M-bit 16M x 8 6ns 8-Pin SOIC Tube")
      (fields
        (field (name "MANUFACTURER") "Winbond")
        (field (name "MANUFACTURER PART NUMBER") "W25Q64JVSSIQ")
      )
      (libsource (lib "eIC") (part "W25Q128JVSIM"))
    )
    (comp (ref "U7")
      (value "ER-TFT1.54-1")
      (footprint "ER-TFT1.54-1")
      (description "1.54\" 240x240 IPS Display")
      (fields (field (name "MANUFACTURER") "Buy Display"))
      (libsource (lib "eDisplay") (part "ER-TFT1.54-1"))
    )
  )
  (nets
    (net (code "1") (name "+1v8") (class "Default")
      (node (ref "C36") (pin "2") (pinfunction "2_2") (pintype "passive"))
      (node (ref "C37") (pin "2") (pinfunction "2_2") (pintype "passive"))
      (node (ref "C38") (pin "2") (pinfunction "2_2") (pintype "passive"))
      (node (ref "C39") (pin "2") (pinfunction "2_2") (pintype "passive"))
      (node (ref "C40") (pin "2") (pinfunction "2_2") (pintype "passive"))
      (node (ref "C41") (pin "2") (pinfunction "2_2") (pintype "passive"))
      (node (ref "C6") (pin "2") (pinfunction "2_2") (pintype "passive"))
      (node (ref "R10") (pin "2") (pinfunction "2_2") (pintype "passive"))
      (node (ref "U1") (pin "A13") (pinfunction "VDD1V8_1_A13") (pintype "power_in"))
      (node (ref "U1") (pin "B11") (pinfunction "VDD1V8_B11") (pintype "power_in"))
      (node (ref "U1") (pin "C16") (pinfunction "VDD1V8_C16") (pintype "power_in"))
      (node (ref "U1") (pin "C17") (pinfunction "VDD1V8_C17") (pintype "power_in"))
      (node (ref "U1") (pin "C4") (pinfunction "VDDA_BIAS_C4") (pintype "power_in"))
      (node (ref "U1") (pin "D2") (pinfunction "VREFP_D2") (pintype "power_in"))
      (node (ref "U1") (pin "E15") (pinfunction "VDD1V8_E15") (pintype "power_in"))
      (node (ref "U1") (pin "E4") (pinfunction "VDDA_ADC1V8_E4") (pintype "power_in"))
      (node (ref "U1") (pin "F13") (pinfunction "VDD1V8_F13") (pintype "power_in"))
      (node (ref "U1") (pin "G14") (pinfunction "VDD1V8_G14") (pintype "power_in"))
      (node (ref "U1") (pin "L4") (pinfunction "VDD1V8_L4") (pintype "power_in"))
      (node (ref "U1") (pin "R15") (pinfunction "VDD1V8_R15") (pintype "power_in"))
    )
    (net (code "2") (name "+1v8_AO") (class "Default")
      (node (ref "C10") (pin "2") (pinfunction "1_2") (pintype "passive"))
      (node (ref "R2") (pin "2") (pinfunction "2_2") (pintype "passive"))
      (node (ref "R5") (pin "2") (pinfunction "2_2") (pintype "passive"))
      (node (ref "U1") (pin "C13") (pinfunction "VDD_AO1V8_C13") (pintype "power_in"))
      (node (ref "U1") (pin "D13") (pinfunction "VDD_AO1V8_D13") (pintype "power_in"))
      (node (ref "U2") (pin "12") (pinfunction "LDO1_OUT_12") (pintype "power_in"))
      (node (ref "U3") (pin "5") (pinfunction "VCC_5") (pintype "passive"))
    )
    (net (code "3") (name "+3v3") (class "Default")
      (node (ref "C12") (pin "2") (pinfunction "2_2") (pintype "passive"))
      (node (ref "C13") (pin "2") (pinfunction "2_2") (pintype "passive"))
      (node (ref "C14") (pin "2") (pinfunction "2_2") (pintype "passive"))
      (node (ref "C15") (pin "2") (pinfunction "2_2") (pintype "passive"))
      (node (ref "C16") (pin "2") (pinfunction "2_2") (pintype "passive"))
      (node (ref "C17") (pin "2") (pinfunction "2_2") (pintype "passive"))
      (node (ref "C18") (pin "2") (pinfunction "1_2") (pintype "passive"))
      (node (ref "C20") (pin "2") (pinfunction "2_2") (pintype "passive"))
      (node (ref "C21") (pin "2") (pinfunction "2_2") (pintype "passive"))
      (node (ref "C22") (pin "2") (pinfunction "2_2") (pintype "passive"))
      (node (ref "C23") (pin "2") (pinfunction "2_2") (pintype "passive"))
      (node (ref "C24") (pin "2") (pinfunction "2_2") (pintype "passive"))
      (node (ref "C25") (pin "2") (pinfunction "2_2") (pintype "passive"))
      (node (ref "C42") (pin "2") (pinfunction "1_2") (pintype "passive"))
      (node (ref "C43") (pin "1") (pinfunction "1_1") (pintype "passive"))
      (node (ref "J3") (pin "1") (pinfunction "VCC_1") (pintype "passive"))
      (node (ref "P10") (pin "1") (pinfunction "1_1") (pintype "passive"))
      (node (ref "R12") (pin "2") (pinfunction "2_2") (pintype "passive"))
      (node (ref "R13") (pin "2") (pinfunction "2_2") (pintype "passive"))
      (node (ref "R14") (pin "2") (pinfunction "2_2") (pintype "passive"))
      (node (ref "R3") (pin "2") (pinfunction "2_2") (pintype "passive"))
      (node (ref "R4") (pin "2") (pinfunction "2_2") (pintype "passive"))
      (node (ref "R8") (pin "2") (pinfunction "2_2") (pintype "passive"))
      (node (ref "U1") (pin "E10") (pinfunction "VDDIO_1_E10") (pintype "power_in"))
      (node (ref "U1") (pin "E6") (pinfunction "VDDIO_1_E6") (pintype "power_in"))
      (node (ref "U1") (pin "E8") (pinfunction "VDDIO_1_E8") (pintype "power_in"))
      (node (ref "U1") (pin "F5") (pinfunction "VDDIO_0_F5") (pintype "power_in"))
      (node (ref "U1") (pin "H13") (pinfunction "VDDIO_1_H13") (pintype "power_in"))
      (node (ref "U1") (pin "H14") (pinfunction "VDDIO_1_H14") (pintype "power_in"))
      (node (ref "U1") (pin "H5") (pinfunction "VDDIO_0_H5") (pintype "power_in"))
      (node (ref "U1") (pin "K13") (pinfunction "VDDIO_1_K13") (pintype "power_in"))
      (node (ref "U1") (pin "K5") (pinfunction "VDDIO_0_K5") (pintype "power_in"))
      (node (ref "U1") (pin "L14") (pinfunction "VDDIO_1_L14") (pintype "power_in"))
      (node (ref "U1") (pin "M5") (pinfunction "VDDIO_0_M5") (pintype "power_in"))
      (node (ref "U1") (pin "N10") (pinfunction "VDDIO_0_N10") (pintype "power_in"))
      (node (ref "U1") (pin "N12") (pinfunction "VDDIO_2_N12") (pintype "power_in"))
      (node (ref "U1") (pin "N16") (pinfunction "USB1_VDD3V3_N16") (pintype "power_in"))
      (node (ref "U1") (pin "N6") (pinfunction "VDDIO_0_N6") (pintype "power_in"))
      (node (ref "U1") (pin "N8") (pinfunction "VDDIO_0_N8") (pintype "power_in"))
      (node (ref "U1") (pin "P11") (pinfunction "VDDIO_2_P11") (pintype "power_in"))
      (node (ref "U1") (pin "P12") (pinfunction "VDDIO_2_P12") (pintype "power_in"))
      (node (ref "U2") (pin "15") (pinfunction "LDO2_OUT_15") (pintype "power_in"))
      (node (ref "U6") (pin "8") (pinfunction "VCC_8") (pintype "passive"))
      (node (ref "U7") (pin "3") (pinfunction "LEDA_3") (pintype "passive"))
      (node (ref "U7") (pin "4") (pinfunction "VDD_4") (pintype "passive"))
    )
    (net (code "4") (name "+5vUSB") (class "Default")
      (node (ref "D2") (pin "1") (pinfunction "A_1") (pintype "passive"))
      (node (ref "L1") (pin "2") (pinfunction "2_2") (pintype "passive"))
      (node (ref "P12") (pin "1") (pinfunction "1_1") (pintype "passive"))
      (node (ref "U1") (pin "R16") (pinfunction "USB1_VBUS_R16") (pintype "input"))
      (node (ref "U4") (pin "4") (pinfunction "VCC_4") (pintype "passive"))
    )
    (net (code "5") (name "+VBATT") (class "Default")
      (node (ref "C4") (pin "2") (pinfunction "1_2") (pintype "passive"))
      (node (ref "J1") (pin "2") (pinfunction "2_2") (pintype "passive"))
      (node (ref "P9") (pin "1") (pinfunction "1_1") (pintype "passive"))
      (node (ref "R6") (pin "2") (pinfunction "2_2") (pintype "passive"))
      (node (ref "U2") (pin "18") (pinfunction "VBAT_18") (pintype "power_in"))
    )
    (net (code "6") (name "+VBATT_BU") (class "Default")
      (node (ref "C3") (pin "2") (pinfunction "1_2") (pintype "passive"))
      (node (ref "R6") (pin "1") (pinfunction "1_1") (pintype "passive"))
      (node (ref "U2") (pin "13") (pinfunction "VBAT_BKUP_13") (pintype "power_in"))
    )
    (net (code "7") (name "+VIN") (class "Default")
      (node (ref "D1") (pin "1") (pinfunction "A_1") (pintype "passive"))
      (node (ref "P11") (pin "1") (pinfunction "1_1") (pintype "passive"))
    )
    (net (code "8") (name "/ADC0_0") (class "Default")
      (node (ref "P43") (pin "1") (pinfunction "1_1") (pintype "passive"))
      (node (ref "U1") (pin "F4") (pinfunction "PIO0_5/FC0_SSEL2/SCT0_GPI0/SCT0_OUT0/CTIMER_INP1/SEC_PIO0_5/ADC0_0_F4") (pintype "passive"))
    )
    (net (code "9") (name "/ADC0_1") (class "Default")
      (node (ref "P45") (pin "1") (pinfunction "1_1") (pintype "passive"))
      (node (ref "U1") (pin "E3") (pinfunction "PIO0_12/FC1_SSEL2/SCT0_GPI2/SCT0_OUT2/CTIMER_INP3/SEC_PIO0_12/ADC0_1_E3") (pintype "passive"))
    )
    (net (code "10") (name "/ADC0_8") (class "Default")
      (node (ref "P44") (pin "1") (pinfunction "1_1") (pintype "passive"))
      (node (ref "U1") (pin "E1") (pinfunction "PIO0_6/FC0_SSEL3/SCT0_GPI1/SCT0_OUT1/CTIMER0_MAT0/SEC_PIO0_6/ADC0_8_E1") (pintype "passive"))
    )
    (net (code "11") (name "/BTN") (class "Default")
      (node (ref "BTN1") (pin "2") (pinfunction "2_2") (pintype "passive"))
      (node (ref "U1") (pin "U17") (pinfunction "PIO2_8/SD0_D7/SCT0_OUT4/CTIMER1_MAT2_U17") (pintype "passive"))
    )
    (net (code "12") (name "/DEBUG_RX_IN") (class "Default")
      (node (ref "P42") (pin "1") (pinfunction "1_1") (pintype "passive"))
      (node (ref "U1") (pin "G4") (pinfunction "PIO0_2/FC0_RXD_SDA_MOSI_DATA/CTIMER0_MAT2/I2S_BRIDGE_DATA_IN/SEC_PIO0_2_G4") (pintype "passive"))
    )
    (net (code "13") (name "/DEBUG_TX_OUT") (class "Default")
      (node (ref "P41") (pin "1") (pinfunction "1_1") (pintype "passive"))
      (node (ref "U1") (pin "G2") (pinfunction "PIO0_1/FC0_TXD_SCL_MISO_WS/CTIMER0_MAT1/I2S_BRIDGE_WS_IN/SEC_PIO0_1_G2") (pintype "passive"))
    )
    (net (code "14") (name "/DM_MCU") (class "Default")
      (node (ref "R9") (pin "2") (pinfunction "2_2") (pintype "passive"))
      (node (ref "U1") (pin "T17") (pinfunction "USB1_DM_T17") (pintype "bidirectional"))
    )
    (net (code "15") (name "/DP_MCU") (class "Default")
      (node (ref "R11") (pin "2") (pinfunction "2_2") (pintype "passive"))
      (node (ref "U1") (pin "R17") (pinfunction "USB1_DP_R17") (pintype "bidirectional"))
    )
    (net (code "16") (name "/FC2_CLK") (class "Default")
      (node (ref "P48") (pin "1") (pinfunction "1_1") (pintype "passive"))
      (node (ref "U1") (pin "A3") (pinfunction "PIO0_14/FC2_SCK/SCT0_GPI0/SCT0_OUT0/CTIMER2_MAT0/I2S_BRIDGE_CLK_IN/SEC_PIO0_14_A3") (pintype "passive"))
    )
    (net (code "17") (name "/FC2_SDA") (class "Default")
      (node (ref "P46") (pin "1") (pinfunction "1_1") (pintype "passive"))
      (node (ref "U1") (pin "D6") (pinfunction "PIO0_16/FC2_RXD_SDA_MOSI_DATA/SCT0_GPI2/SCT0_OUT2/CTIMER2_MAT2/I2S_BRIDGE_DATA_IN/SEC_PIO0_16_D6") (pintype "passive"))
    )
    (net (code "18") (name "/FC2_WS") (class "Default")
      (node (ref "P47") (pin "1") (pinfunction "1_1") (pintype "passive"))
      (node (ref "U1") (pin "A5") (pinfunction "PIO0_15/FC2_TXD_SCL_MISO_WS/SCT0_GPI1/SCT0_OUT1/CTIMER2_MAT1/I2S_BRIDGE_WS_IN/SEC_PIO0_15_A5") (pintype "passive"))
    )
    (net (code "19") (name "/FC3_CLK") (class "Default")
      (node (ref "P1") (pin "1") (pinfunction "1_1") (pintype "passive"))
      (node (ref "U1") (pin "C7") (pinfunction "PIO0_21/FC3_SCK/CTIMER3_MAT0/TRACECLK/SEC_PIO0_21_C7") (pintype "passive"))
    )
    (net (code "20") (name "/FC3_SDA") (class "Default")
      (node (ref "P3") (pin "1") (pinfunction "1_1") (pintype "passive"))
      (node (ref "U1") (pin "C9") (pinfunction "PIO0_23/FC3_RXD_SDA_MOSI_DATA/CTIMER3_MAT2/TRACEDATA(1)/SEC_PIO0_23_C9") (pintype "passive"))
    )
    (net (code "21") (name "/FC3_WS") (class "Default")
      (node (ref "P2") (pin "1") (pinfunction "1_1") (pintype "passive"))
      (node (ref "U1") (pin "D8") (pinfunction "PIO0_22/FC3_TXD_SCL_MISO_WS/CTIMER3_MAT1/TRACEDATA(0)/SEC_PIO0_22_D8") (pintype "passive"))
    )
    (net (code "22") (name "/FC4_CLK") (class "Default")
      (node (ref "U1") (pin "D11") (pinfunction "PIO0_28/FC4_SCK/CTIMER4_MAT0/I2S_BRIDGE_CLK_OUT/SEC_PIO0_28_D11") (pintype "passive"))
    )
    (net (code "23") (name "/FC4_SDA") (class "Default")
      (node (ref "U1") (pin "C11") (pinfunction "PIO0_30/FC4_RXD_SDA_MOSI_DATA/CTIMER4_MAT2/I2S_BRIDGE_DATA_OUT/SEC_PIO0_30_C11") (pintype "passive"))
    )
    (net (code "24") (name "/FC4_WS") (class "Default")
      (node (ref "U1") (pin "B10") (pinfunction "PIO0_29/FC4_TXD_SCL_MISO_WS/CTIMER4_MAT1/I2S_BRIDGE_WS_OUT/SEC_PIO0_29_B10") (pintype "passive"))
    )
    (net (code "25") (name "/FC5_RXD") (class "Default")
      (node (ref "P6") (pin "1") (pinfunction "1_1") (pintype "passive"))
      (node (ref "U1") (pin "J16") (pinfunction "PIO1_5/FC5_RXD_SDA_MOSI_DATA_J16") (pintype "passive"))
    )
    (net (code "26") (name "/FC5_SCK") (class "Default")
      (node (ref "P4") (pin "1") (pinfunction "1_1") (pintype "passive"))
      (node (ref "U1") (pin "G16") (pinfunction "PIO1_3/FC5_SCK_G16") (pintype "passive"))
    )
    (net (code "27") (name "/FC5_SSEL0") (class "Default")
      (node (ref "P7") (pin "1") (pinfunction "1_1") (pintype "passive"))
      (node (ref "U1") (pin "J17") (pinfunction "PIO1_6/FC5_CTS_SDA_SSEL0/SCT0_GPI4/SCT0_OUT4/FC4_SSEL2_J17") (pintype "passive"))
    )
    (net (code "28") (name "/FC5_TXD") (class "Default")
      (node (ref "P5") (pin "1") (pinfunction "1_1") (pintype "passive"))
      (node (ref "U1") (pin "G17") (pinfunction "PIO1_4/FC5_TXD_SCL_MISO_WS_G17") (pintype "passive"))
    )
    (net (code "29") (name "/HS_SPI_MISO") (class "Default")
      (node (ref "U1") (pin "M2") (pinfunction "PIO1_12/HS_SPI_MISO/CTIMER2_MAT1/FLEXSPI0B_DATA1_M2") (pintype "passive"))
    )
    (net (code "30") (name "/HS_SPI_MOSI") (class "Default")
      (node (ref "U1") (pin "N1") (pinfunction "PIO1_13/HS_SPI_MOSI/CTIMER2_MAT2/FLEXSPI0B_DATA2_N1") (pintype "passive"))
      (node (ref "U7") (pin "10") (pinfunction "SDA_10") (pintype "passive"))
    )
    (net (code "31") (name "/HS_SPI_SCK") (class "Default")
      (node (ref "U1") (pin "L2") (pinfunction "PIO1_11/HS_SPI_SCK/CTIMER2_MAT0/FLEXSPI0B_DATA0_L2") (pintype "passive"))
      (node (ref "U7") (pin "9") (pinfunction "SCL_9") (pintype "passive"))
    )
    (net (code "32") (name "/HS_SPI_SSEL0") (class "Default")
      (node (ref "U1") (pin "N2") (pinfunction "PIO1_14/HS_SPI_SSEL0/CTIMER2_MAT3/FLEXSPI0B_DATA3_N2") (pintype "passive"))
      (node (ref "U7") (pin "8") (pinfunction "CS_8") (pintype "passive"))
    )
    (net (code "33") (name "/I3C0_PUR") (class "Default")
      (node (ref "R16") (pin "1") (pinfunction "1_1") (pintype "passive"))
      (node (ref "U1") (pin "B6") (pinfunction "PIO2_31/I3C0_PUR/SCT0_OUT7/UTICK_CAP3/CTIMER_INP15/SWO/CMP0_B_B6") (pintype "passive"))
    )
    (net (code "34") (name "/I3C0_SCL") (class "Default")
      (node (ref "P15") (pin "1") (pinfunction "1_1") (pintype "passive"))
      (node (ref "U1") (pin "N17") (pinfunction "PIO2_29/I3C0_SCL/SCT0_OUT0/CLKOUT_N17") (pintype "passive"))
    )
    (net (code "35") (name "/I3C0_SDA") (class "Default")
      (node (ref "P16") (pin "1") (pinfunction "1_1") (pintype "passive"))
      (node (ref "R16") (pin "2") (pinfunction "2_2") (pintype "passive"))
      (node (ref "U1") (pin "P16") (pinfunction "PIO2_30/I3C0_SDA/SCT0_OUT3/CLKIN/CMP0_OUT_P16") (pintype "passive"))
    )
    (net (code "36") (name "/ISP0") (class "Default")
      (node (ref "R12") (pin "1") (pinfunction "1_1") (pintype "passive"))
      (node (ref "SW1") (pin "2") (pinfunction "2_2") (pintype "passive"))
      (node (ref "U1") (pin "N3") (pinfunction "PIO1_15/HS_SPI_SSEL1/CTIMER3_MAT0/ISP0_N3") (pintype "passive"))
    )
    (net (code "37") (name "/ISP1") (class "Default")
      (node (ref "R13") (pin "1") (pinfunction "1_1") (pintype "passive"))
      (node (ref "SW2") (pin "2") (pinfunction "2_2") (pintype "passive"))
      (node (ref "U1") (pin "M4") (pinfunction "PIO1_16/HS_SPI_SSEL2/SCT0_OUT8/CTIMER3_MAT1/ISP1_M4") (pintype "passive"))
    )
    (net (code "38") (name "/ISP2") (class "Default")
      (node (ref "R14") (pin "1") (pinfunction "1_1") (pintype "passive"))
      (node (ref "SW3") (pin "2") (pinfunction "2_2") (pintype "passive"))
      (node (ref "U1") (pin "N4") (pinfunction "PIO1_17/HS_SPI_SSEL3/SCT0_OUT9/CTIMER3_MAT2/ISP2_N4") (pintype "passive"))
    )
    (net (code "39") (name "/LCD_BL") (class "Default")
      (node (ref "Q1") (pin "1") (pinfunction "G_1") (pintype "passive"))
      (node (ref "U1") (pin "U16") (pinfunction "PIO2_7/SD0_D6/SCT0_GPI5/CTIMER1_MAT1_U16") (pintype "passive"))
    )
    (net (code "40") (name "/LCD_CMD_DATA") (class "Default")
      (node (ref "U1") (pin "U13") (pinfunction "PIO2_5/SD0_D4/SCT0_OUT3_U13") (pintype "passive"))
      (node (ref "U7") (pin "7") (pinfunction "D/C_7") (pintype "passive"))
    )
    (net (code "41") (name "/LCD_RST") (class "Default")
      (node (ref "U1") (pin "U15") (pinfunction "PIO2_6/SD0_D5/SCT0_GPI4/CTIMER1_MAT0_U15") (pintype "passive"))
      (node (ref "U7") (pin "11") (pinfunction "RESET_11") (pintype "passive"))
    )
    (net (code "42") (name "/MCLK") (class "Default")
      (node (ref "P14") (pin "1") (pinfunction "1_1") (pintype "passive"))
      (node (ref "U1") (pin "K16") (pinfunction "PIO1_10/MCLK/FREQME_GPIO_CLK/CTIMER_INP10/CLKOUT_K16") (pintype "passive"))
    )
    (net (code "43") (name "/PDM_CLK01") (class "Default")
      (node (ref "P38") (pin "1") (pinfunction "1_1") (pintype "passive"))
      (node (ref "U1") (pin "R1") (pinfunction "PIO2_16/PDM_CLK01_R1") (pintype "passive"))
    )
    (net (code "44") (name "/PDM_CLK23") (class "Default")
      (node (ref "P36") (pin "1") (pinfunction "1_1") (pintype "passive"))
      (node (ref "U1") (pin "U1") (pinfunction "PIO2_17/PDM_CLK23/FLEXSPI0B_DATA4_U1") (pintype "passive"))
    )
    (net (code "45") (name "/PDM_CLK45") (class "Default")
      (node (ref "P34") (pin "1") (pinfunction "1_1") (pintype "passive"))
      (node (ref "U1") (pin "R2") (pinfunction "PIO2_18/PDM_CLK45/FLEXSPI0B_DATA5_R2") (pintype "passive"))
    )
    (net (code "46") (name "/PDM_CLK67") (class "Default")
      (node (ref "P32") (pin "1") (pinfunction "1_1") (pintype "passive"))
      (node (ref "U1") (pin "T2") (pinfunction "PIO2_19/PDM_CLK67/FLEXSPI0B_SS0_N_T2") (pintype "passive"))
    )
    (net (code "47") (name "/PDM_DATA01") (class "Default")
      (node (ref "P37") (pin "1") (pinfunction "1_1") (pintype "passive"))
      (node (ref "U1") (pin "U2") (pinfunction "PIO2_20/PDM_DATA01_U2") (pintype "passive"))
    )
    (net (code "48") (name "/PDM_DATA23") (class "Default")
      (node (ref "P35") (pin "1") (pinfunction "1_1") (pintype "passive"))
      (node (ref "U1") (pin "R3") (pinfunction "PIO2_21/PDM_DATA23/CTIMER_INP14/FLEXSPI0B_SS1_N_R3") (pintype "passive"))
    )
    (net (code "49") (name "/PDM_DATA45") (class "Default")
      (node (ref "P33") (pin "1") (pinfunction "1_1") (pintype "passive"))
      (node (ref "U1") (pin "P3") (pinfunction "PIO2_22/PDM_DATA45/FLEXSPI0B_DATA6_P3") (pintype "passive"))
    )
    (net (code "50") (name "/PDM_DATA67") (class "Default")
      (node (ref "P31") (pin "1") (pinfunction "1_1") (pintype "passive"))
      (node (ref "U1") (pin "P5") (pinfunction "PIO2_23/PDM_DATA67/FLEXSPI0B_DATA7_P5") (pintype "passive"))
    )
    (net (code "51") (name "/PIO0_11") (class "Default")
      (node (ref "P39") (pin "1") (pinfunction "1_1") (pintype "passive"))
      (node (ref "U1") (pin "L1") (pinfunction "PIO0_11/FC1_RTS_SCL_SSEL1/SCT0_GPI0/SCT0_OUT8/CTIMER_INP2/FC0_SSEL3/SEC_PIO0_11_L1") (pintype "passive"))
    )
    (net (code "52") (name "/PIO1_8") (class "Default")
      (node (ref "TP6") (pin "1") (pinfunction "1_1") (pintype "passive"))
      (node (ref "U1") (pin "B5") (pinfunction "PIO1_8/FC5_SSEL2/SCT0_GPI6/CTIMER_INP12/CTIMER1_MAT2/ADC0_4_B5") (pintype "passive"))
    )
    (net (code "53") (name "/PIO1_9") (class "Default")
      (node (ref "TP7") (pin "1") (pinfunction "1_1") (pintype "passive"))
      (node (ref "U1") (pin "B1") (pinfunction "PIO1_9/FC5_SSEL3/SCT0_GPI7/UTICK_CAP1/CTIMER1_MAT3/ADC0_12_B1") (pintype "passive"))
    )
    (net (code "54") (name "/PMIC_INTB") (class "Default")
      (node (ref "R2") (pin "1") (pinfunction "1_1") (pintype "passive"))
      (node (ref "U1") (pin "A15") (pinfunction "~{PMIC_IRQ_N}_A15") (pintype "input"))
      (node (ref "U2") (pin "10") (pinfunction "INTB_10") (pintype "output"))
    )
    (net (code "55") (name "/PMIC_MODE0") (class "Default")
      (node (ref "U1") (pin "C15") (pinfunction "PMIC_MODE0_C15") (pintype "output"))
      (node (ref "U2") (pin "7") (pinfunction "MODESEL0_7") (pintype "input"))
    )
    (net (code "56") (name "/PMIC_MODE1") (class "Default")
      (node (ref "U1") (pin "B16") (pinfunction "PMIC_MODE1_B16") (pintype "output"))
      (node (ref "U2") (pin "8") (pinfunction "MODESEL1_8") (pintype "input"))
    )
    (net (code "57") (name "/PMIC_ON") (class "Default")
      (node (ref "P13") (pin "1") (pinfunction "1_1") (pintype "passive"))
      (node (ref "U2") (pin "4") (pinfunction "ON_4") (pintype "input"))
    )
    (net (code "58") (name "/PMIC_RESETN") (class "Default")
      (node (ref "R5") (pin "1") (pinfunction "1_1") (pintype "passive"))
      (node (ref "U1") (pin "B15") (pinfunction "~{RESETN}_B15") (pintype "input"))
      (node (ref "U2") (pin "11") (pinfunction "SYSRSTN_11") (pintype "output"))
      (node (ref "U3") (pin "4") (pinfunction "Y_4") (pintype "passive"))
    )
    (net (code "59") (name "/PMIC_SCL") (class "Default")
      (node (ref "R3") (pin "1") (pinfunction "1_1") (pintype "passive"))
      (node (ref "U1") (pin "E16") (pinfunction "PMIC_I2C_SCL_E16") (pintype "output"))
      (node (ref "U2") (pin "5") (pinfunction "SCL_5") (pintype "input"))
    )
    (net (code "60") (name "/PMIC_SDA") (class "Default")
      (node (ref "R4") (pin "1") (pinfunction "1_1") (pintype "passive"))
      (node (ref "U1") (pin "F16") (pinfunction "PMIC_I2C_SDA_F16") (pintype "bidirectional"))
      (node (ref "U2") (pin "6") (pinfunction "SDA_6") (pintype "bidirectional"))
    )
    (net (code "61") (name "/QSPI_CS") (class "Default")
      (node (ref "U1") (pin "T4") (pinfunction "PIO1_19/FLEXSPI0A_SS0_N/SCT0_OUT0/CTIMER4_MAT0_T4") (pintype "passive"))
      (node (ref "U6") (pin "1") (pinfunction "~{CE}_1") (pintype "passive"))
    )
    (net (code "62") (name "/QSPI_D0") (class "Default")
      (node (ref "U1") (pin "T5") (pinfunction "PIO1_20/FLEXSPI0A_DATA0/SCT0_GPI1/CTIMER4_MAT1_T5") (pintype "passive"))
      (node (ref "U6") (pin "5") (pinfunction "SI_(IO0)_5") (pintype "passive"))
    )
    (net (code "63") (name "/QSPI_D1") (class "Default")
      (node (ref "U1") (pin "U5") (pinfunction "PIO1_21/FLEXSPI0A_DATA1/SCT0_OUT1/CTIMER4_MAT2_U5") (pintype "passive"))
      (node (ref "U6") (pin "2") (pinfunction "SO_(IO1)_2") (pintype "passive"))
    )
    (net (code "64") (name "/QSPI_D2") (class "Default")
      (node (ref "U1") (pin "P6") (pinfunction "PIO1_22/FLEXSPI0A_DATA2/SCT0_GPI2/CTIMER4_MAT3_P6") (pintype "passive"))
      (node (ref "U6") (pin "3") (pinfunction "~{WP}_(IO2)_3") (pintype "passive"))
    )
    (net (code "65") (name "/QSPI_D3") (class "Default")
      (node (ref "U1") (pin "P7") (pinfunction "PIO1_23/FLEXSPI0A_DATA3/SCT0_OUT2/CTIMER_INP8_P7") (pintype "passive"))
      (node (ref "U6") (pin "7") (pinfunction "~{HOLD}_(IO3)_7") (pintype "passive"))
    )
    (net (code "66") (name "/QSPI_SCK") (class "Default")
      (node (ref "U1") (pin "T9") (pinfunction "PIO1_18/FLEXSPI0A_SCLK/SCT0_GPI0/CTIMER3_MAT3_T9") (pintype "passive"))
      (node (ref "U6") (pin "6") (pinfunction "SCK_6") (pintype "passive"))
    )
    (net (code "67") (name "/RST_3V3") (class "Default")
      (node (ref "J3") (pin "10") (pinfunction "~{RST}_10") (pintype "passive"))
      (node (ref "P20") (pin "1") (pinfunction "1_1") (pintype "passive"))
      (node (ref "R8") (pin "1") (pinfunction "1_1") (pintype "passive"))
      (node (ref "RESET1") (pin "2") (pinfunction "2_2") (pintype "passive"))
      (node (ref "U3") (pin "2") (pinfunction "A_2") (pintype "passive"))
    )
    (net (code "68") (name "/SD_CLK") (class "Default")
      (node (ref "P25") (pin "1") (pinfunction "1_1") (pintype "passive"))
      (node (ref "U1") (pin "P10") (pinfunction "PIO1_30/SD0_CLK/SCT0_GPI0_P10") (pintype "passive"))
    )
    (net (code "69") (name "/SD_CMD") (class "Default")
      (node (ref "P30") (pin "1") (pinfunction "1_1") (pintype "passive"))
      (node (ref "U1") (pin "R9") (pinfunction "PIO1_31/SD0_CMD/SCT0_GPI1_R9") (pintype "passive"))
    )
    (net (code "70") (name "/SD_D0") (class "Default")
      (node (ref "P29") (pin "1") (pinfunction "1_1") (pintype "passive"))
      (node (ref "U1") (pin "R11") (pinfunction "PIO2_0/SD0_D0/SCT0_GPI2_R11") (pintype "passive"))
    )
    (net (code "71") (name "/SD_D1") (class "Default")
      (node (ref "P28") (pin "1") (pinfunction "1_1") (pintype "passive"))
      (node (ref "U1") (pin "T11") (pinfunction "PIO2_1/SD0_D1/SCT0_GPI3_T11") (pintype "passive"))
    )
    (net (code "72") (name "/SD_D2") (class "Default")
      (node (ref "P27") (pin "1") (pinfunction "1_1") (pintype "passive"))
      (node (ref "U1") (pin "U11") (pinfunction "PIO2_2/SD0_D2/SCT0_OUT0_U11") (pintype "passive"))
    )
    (net (code "73") (name "/SD_D3") (class "Default")
      (node (ref "P26") (pin "1") (pinfunction "1_1") (pintype "passive"))
      (node (ref "U1") (pin "T12") (pinfunction "PIO2_3/SD0_D3/SCT0_OUT1_T12") (pintype "passive"))
    )
    (net (code "74") (name "/SD_DETECT_N") (class "Default")
      (node (ref "P24") (pin "1") (pinfunction "1_1") (pintype "passive"))
      (node (ref "U1") (pin "R13") (pinfunction "PIO2_9/SD0_CARD_DET_N/SCT0_OUT5/CTIMER1_MAT3_R13") (pintype "passive"))
    )
    (net (code "75") (name "/SD_RESET_N") (class "Default")
      (node (ref "P23") (pin "1") (pinfunction "1_1") (pintype "passive"))
      (node (ref "U1") (pin "T15") (pinfunction "PIO2_10/SD0_RESET_N/SCT0_GPI6/CTIMER2_MAT0_T15") (pintype "passive"))
    )
    (net (code "76") (name "/SWCLK") (class "Default")
      (node (ref "J3") (pin "4") (pinfunction "SWDCLK/TCK_4") (pintype "passive"))
      (node (ref "P22") (pin "1") (pinfunction "1_1") (pintype "passive"))
      (node (ref "U1") (pin "L17") (pinfunction "PIO2_25/SWCLK_L17") (pintype "passive"))
    )
    (net (code "77") (name "/SWIO") (class "Default")
      (node (ref "J3") (pin "2") (pinfunction "SWDIO/TMS_2") (pintype "passive"))
      (node (ref "P21") (pin "1") (pinfunction "1_1") (pintype "passive"))
      (node (ref "U1") (pin "L15") (pinfunction "PIO2_26/SWDIO_L15") (pintype "passive"))
    )
    (net (code "78") (name "/SWO") (class "Default")
      (node (ref "J3") (pin "6") (pinfunction "SWO/TDO_6") (pintype "passive"))
      (node (ref "U1") (pin "L16") (pinfunction "PIO2_24/SWO/GPIO_INT_BMAT_L16") (pintype "passive"))
    )
    (net (code "79") (name "/TEMP_SENSE") (class "Default")
      (node (ref "TP1") (pin "1") (pinfunction "1_1") (pintype "passive"))
      (node (ref "U2") (pin "14") (pinfunction "TS_14") (pintype "input"))
    )
    (net (code "80") (name "GND") (class "Default")
      (node (ref "BTN1") (pin "1") (pinfunction "1_1") (pintype "passive"))
      (node (ref "BTN1") (pin "S") (pinfunction "SHIELD_S") (pintype "passive"))
      (node (ref "C1") (pin "1") (pinfunction "1_1") (pintype "passive"))
      (node (ref "C10") (pin "1") (pinfunction "1_1") (pintype "passive"))
      (node (ref "C11") (pin "1") (pinfunction "1_1") (pintype "passive"))
      (node (ref "C12") (pin "1") (pinfunction "1_1") (pintype "passive"))
      (node (ref "C13") (pin "1") (pinfunction "1_1") (pintype "passive"))
      (node (ref "C14") (pin "1") (pinfunction "1_1") (pintype "passive"))
      (node (ref "C15") (pin "1") (pinfunction "1_1") (pintype "passive"))
      (node (ref "C16") (pin "1") (pinfunction "1_1") (pintype "passive"))
      (node (ref "C17") (pin "1") (pinfunction "1_1") (pintype "passive"))
      (node (ref "C18") (pin "1") (pinfunction "1_1") (pintype "passive"))
      (node (ref "C19") (pin "1") (pinfunction "1_1") (pintype "passive"))
      (node (ref "C2") (pin "2") (pinfunction "1_2") (pintype "passive"))
      (node (ref "C20") (pin "1") (pinfunction "1_1") (pintype "passive"))
      (node (ref "C21") (pin "1") (pinfunction "1_1") (pintype "passive"))
      (node (ref "C22") (pin "1") (pinfunction "1_1") (pintype "passive"))
      (node (ref "C23") (pin "1") (pinfunction "1_1") (pintype "passive"))
      (node (ref "C24") (pin "1") (pinfunction "1_1") (pintype "passive"))
      (node (ref "C25") (pin "1") (pinfunction "1_1") (pintype "passive"))
      (node (ref "C26") (pin "1") (pinfunction "1_1") (pintype "passive"))
      (node (ref "C27") (pin "1") (pinfunction "1_1") (pintype "passive"))
      (node (ref "C28") (pin "1") (pinfunction "1_1") (pintype "passive"))
      (node (ref "C29") (pin "1") (pinfunction "1_1") (pintype "passive"))
      (node (ref "C3") (pin "1") (pinfunction "1_1") (pintype "passive"))
      (node (ref "C30") (pin "1") (pinfunction "1_1") (pintype "passive"))
      (node (ref "C31") (pin "1") (pinfunction "1_1") (pintype "passive"))
      (node (ref "C32") (pin "1") (pinfunction "1_1") (pintype "passive"))
      (node (ref "C33") (pin "1") (pinfunction "1_1") (pintype "passive"))
      (node (ref "C34") (pin "1") (pinfunction "1_1") (pintype "passive"))
      (node (ref "C35") (pin "1") (pinfunction "1_1") (pintype "passive"))
      (node (ref "C36") (pin "1") (pinfunction "1_1") (pintype "passive"))
      (node (ref "C37") (pin "1") (pinfunction "1_1") (pintype "passive"))
      (node (ref "C38") (pin "1") (pinfunction "1_1") (pintype "passive"))
      (node (ref "C39") (pin "1") (pinfunction "1_1") (pintype "passive"))
      (node (ref "C4") (pin "1") (pinfunction "1_1") (pintype "passive"))
      (node (ref "C40") (pin "1") (pinfunction "1_1") (pintype "passive"))
      (node (ref "C41") (pin "1") (pinfunction "1_1") (pintype "passive"))
      (node (ref "C42") (pin "1") (pinfunction "1_1") (pintype "passive"))
      (node (ref "C43") (pin "2") (pinfunction "1_2") (pintype "passive"))
      (node (ref "C5") (pin "2") (pinfunction "1_2") (pintype "passive"))
      (node (ref "C6") (pin "1") (pinfunction "1_1") (pintype "passive"))
      (node (ref "C7") (pin "1") (pinfunction "1_1") (pintype "passive"))
      (node (ref "C8") (pin "2") (pinfunction "1_2") (pintype "passive"))
      (node (ref "C9") (pin "1") (pinfunction "1_1") (pintype "passive"))
      (node (ref "J1") (pin "1") (pinfunction "1_1") (pintype "passive"))
      (node (ref "J2") (pin "4") (pinfunction "ID_4") (pintype "passive"))
      (node (ref "J2") (pin "5") (pinfunction "GND_5") (pintype "passive"))
      (node (ref "J2") (pin "MOUNT") (pinfunction "MOUNT_MOUNT") (pintype "passive"))
      (node (ref "J3") (pin "3") (pinfunction "GND_3") (pintype "passive"))
      (node (ref "J3") (pin "5") (pinfunction "GND_5") (pintype "passive"))
      (node (ref "J3") (pin "9") (pinfunction "GND_DETECT_9") (pintype "passive"))
      (node (ref "P40") (pin "1") (pinfunction "1_1") (pintype "passive"))
      (node (ref "P8") (pin "1") (pinfunction "1_1") (pintype "passive"))
      (node (ref "Q1") (pin "2") (pinfunction "2_2") (pintype "passive"))
      (node (ref "R1") (pin "1") (pinfunction "1_1") (pintype "passive"))
      (node (ref "RESET1") (pin "1") (pinfunction "1_1") (pintype "passive"))
      (node (ref "RESET1") (pin "S") (pinfunction "SHIELD_S") (pintype "passive"))
      (node (ref "SW1") (pin "1") (pinfunction "1_1") (pintype "passive"))
      (node (ref "SW2") (pin "1") (pinfunction "1_1") (pintype "passive"))
      (node (ref "SW3") (pin "1") (pinfunction "1_1") (pintype "passive"))
      (node (ref "U1") (pin "C2") (pinfunction "VREFN_C2") (pintype "power_in"))
      (node (ref "U1") (pin "C3") (pinfunction "VSSA_C3") (pintype "power_in"))
      (node (ref "U1") (pin "D12") (pinfunction "VSSA_D12") (pintype "power_in"))
      (node (ref "U1") (pin "D15") (pinfunction "VSS_D15") (pintype "power_in"))
      (node (ref "U1") (pin "D5") (pinfunction "VSS_D5") (pintype "power_in"))
      (node (ref "U1") (pin "E12") (pinfunction "VSS_E12") (pintype "power_in"))
      (node (ref "U1") (pin "E14") (pinfunction "VSS_E14") (pintype "power_in"))
      (node (ref "U1") (pin "F11") (pinfunction "VSS_F11") (pintype "power_in"))
      (node (ref "U1") (pin "F7") (pinfunction "VSS_F7") (pintype "power_in"))
      (node (ref "U1") (pin "G12") (pinfunction "VSS_G12") (pintype "power_in"))
      (node (ref "U1") (pin "G6") (pinfunction "VSS_G6") (pintype "power_in"))
      (node (ref "U1") (pin "H10") (pinfunction "VSS_H10") (pintype "power_in"))
      (node (ref "U1") (pin "H8") (pinfunction "VSS_H8") (pintype "power_in"))
      (node (ref "U1") (pin "H9") (pinfunction "VSS_H9") (pintype "power_in"))
      (node (ref "U1") (pin "J10") (pinfunction "VSS_J10") (pintype "power_in"))
      (node (ref "U1") (pin "J8") (pinfunction "VSS_J8") (pintype "power_in"))
      (node (ref "U1") (pin "K10") (pinfunction "VSS_K10") (pintype "power_in"))
      (node (ref "U1") (pin "K8") (pinfunction "VSS_K8") (pintype "power_in"))
      (node (ref "U1") (pin "K9") (pinfunction "VSS_K9") (pintype "power_in"))
      (node (ref "U1") (pin "L12") (pinfunction "VSS_L12") (pintype "power_in"))
      (node (ref "U1") (pin "L6") (pinfunction "VSS_L6") (pintype "power_in"))
      (node (ref "U1") (pin "M11") (pinfunction "VSS_M11") (pintype "power_in"))
      (node (ref "U1") (pin "M13") (pinfunction "VSS_M13") (pintype "power_in"))
      (node (ref "U1") (pin "M7") (pinfunction "VSS_M7") (pintype "power_in"))
      (node (ref "U1") (pin "N14") (pinfunction "VSS_N14") (pintype "power_in"))
      (node (ref "U1") (pin "P13") (pinfunction "VSS_P13") (pintype "power_in"))
      (node (ref "U2") (pin "21") (pinfunction "AGND2_21") (pintype "power_in"))
      (node (ref "U2") (pin "23") (pinfunction "PGND1_23") (pintype "power_in"))
      (node (ref "U2") (pin "24") (pinfunction "PGND2_24") (pintype "power_in"))
      (node (ref "U2") (pin "25") (pinfunction "EXP_25") (pintype "power_in"))
      (node (ref "U2") (pin "9") (pinfunction "AGND1_9") (pintype "power_in"))
      (node (ref "U3") (pin "3") (pinfunction "GND_3") (pintype "passive"))
      (node (ref "U4") (pin "1") (pinfunction "GND_1") (pintype "passive"))
      (node (ref "U6") (pin "4") (pinfunction "GND_4") (pintype "passive"))
      (node (ref "U7") (pin "1") (pinfunction "GND_1") (pintype "passive"))
      (node (ref "U7") (pin "12") (pinfunction "GND_12") (pintype "passive"))
      (node (ref "U7") (pin "5") (pinfunction "GND_5") (pintype "passive"))
      (node (ref "U7") (pin "6") (pinfunction "GND_6") (pintype "passive"))
    )
    (net (code "81") (name "Net-(D1-K)") (class "Default")
      (node (ref "C1") (pin "2") (pinfunction "1_2") (pintype "passive"))
      (node (ref "D1") (pin "2") (pinfunction "K_2") (pintype "passive"))
      (node (ref "D2") (pin "2") (pinfunction "K_2") (pintype "passive"))
      (node (ref "U2") (pin "16") (pinfunction "VIN_16") (pintype "power_in"))
    )
    (net (code "82") (name "Net-(J2-+5v)") (class "Default")
      (node (ref "J2") (pin "1") (pinfunction "+5v_1") (pintype "passive"))
      (node (ref "L1") (pin "1") (pinfunction "1_1") (pintype "passive"))
    )
    (net (code "83") (name "Net-(J2-D+)") (class "Default")
      (node (ref "J2") (pin "3") (pinfunction "D+_3") (pintype "passive"))
      (node (ref "R11") (pin "1") (pinfunction "1_1") (pintype "passive"))
      (node (ref "U4") (pin "3") (pinfunction "IO2_3") (pintype "passive"))
    )
    (net (code "84") (name "Net-(J2-D-)") (class "Default")
      (node (ref "J2") (pin "2") (pinfunction "D-_2") (pintype "passive"))
      (node (ref "R9") (pin "1") (pinfunction "1_1") (pintype "passive"))
      (node (ref "U4") (pin "2") (pinfunction "IO1_2") (pintype "passive"))
    )
    (net (code "85") (name "Net-(Q1-D)") (class "Default")
      (node (ref "Q1") (pin "3") (pinfunction "D_3") (pintype "passive"))
      (node (ref "R15") (pin "1") (pinfunction "1_1") (pintype "passive"))
    )
    (net (code "86") (name "Net-(U1C-LDO_ENABLE)") (class "Default")
      (node (ref "R1") (pin "2") (pinfunction "2_2") (pintype "passive"))
      (node (ref "U1") (pin "A16") (pinfunction "LDO_ENABLE_A16") (pintype "input"))
    )
    (net (code "87") (name "Net-(U1D-PIO0_4{slash}FC0_RTS_SCL_SSEL1{slash}CTIMER_INP0{slash}FC1_SSEL3{slash}CMP0_OUT{slash}SEC_PIO0_4)") (class "Default")
      (node (ref "TP2") (pin "1") (pinfunction "1_1") (pintype "passive"))
      (node (ref "U1") (pin "J1") (pinfunction "PIO0_4/FC0_RTS_SCL_SSEL1/CTIMER_INP0/FC1_SSEL3/CMP0_OUT/SEC_PIO0_4_J1") (pintype "passive"))
    )
    (net (code "88") (name "Net-(U1D-PIO2_14{slash}SCT0_OUT8{slash}CTIMER_INP1{slash}CMP0_A)") (class "Default")
      (node (ref "TP3") (pin "1") (pinfunction "1_1") (pintype "passive"))
      (node (ref "U1") (pin "C1") (pinfunction "PIO2_14/SCT0_OUT8/CTIMER_INP1/CMP0_A_C1") (pintype "passive"))
    )
    (net (code "89") (name "Net-(U1E-PIO0_19{slash}FC2_SSEL2{slash}SCT0_GPI4{slash}SCT0_OUT4{slash}CTIMER_INP5{slash}UTICK_CAP0{slash}SEC_PIO0_19{slash}ADC0_2)") (class "Default")
      (node (ref "TP4") (pin "1") (pinfunction "1_1") (pintype "passive"))
      (node (ref "U1") (pin "A1") (pinfunction "PIO0_19/FC2_SSEL2/SCT0_GPI4/SCT0_OUT4/CTIMER_INP5/UTICK_CAP0/SEC_PIO0_19/ADC0_2_A1") (pintype "passive"))
    )
    (net (code "90") (name "Net-(U1E-PIO0_26{slash}FC3_SSEL2{slash}SCT0_GPI6{slash}SCT0_OUT6{slash}CTIMER_INP7{slash}SEC_PIO0_26{slash}ADC0_3)") (class "Default")
      (node (ref "TP5") (pin "1") (pinfunction "1_1") (pintype "passive"))
      (node (ref "U1") (pin "A2") (pinfunction "PIO0_26/FC3_SSEL2/SCT0_GPI6/SCT0_OUT6/CTIMER_INP7/SEC_PIO0_26/ADC0_3_A2") (pintype "passive"))
    )
    (net (code "91") (name "Net-(U1H-XTALIN)") (class "Default")
      (node (ref "C11") (pin "2") (pinfunction "1_2") (pintype "passive"))
      (node (ref "U1") (pin "B14") (pinfunction "XTALIN_B14") (pintype "input"))
      (node (ref "U5") (pin "2") (pinfunction "OSC2_2") (pintype "passive"))
    )
    (net (code "92") (name "Net-(U1H-XTALOUT)") (class "Default")
      (node (ref "C19") (pin "2") (pinfunction "1_2") (pintype "passive"))
      (node (ref "U1") (pin "B13") (pinfunction "XTALOUT_B13") (pintype "output"))
      (node (ref "U5") (pin "1") (pinfunction "OSC1_1") (pintype "passive"))
    )
    (net (code "93") (name "Net-(U2-ASYS)") (class "Default")
      (node (ref "C2") (pin "1") (pinfunction "1_1") (pintype "passive"))
      (node (ref "C5") (pin "1") (pinfunction "1_1") (pintype "passive"))
      (node (ref "C8") (pin "1") (pinfunction "1_1") (pintype "passive"))
      (node (ref "U2") (pin "17") (pinfunction "ASYS_17") (pintype "power_in"))
      (node (ref "U2") (pin "2") (pinfunction "PSYS2_2") (pintype "power_in"))
      (node (ref "U2") (pin "20") (pinfunction "PSYS1_20") (pintype "power_in"))
    )
    (net (code "94") (name "Net-(U2-LX1)") (class "Default")
      (node (ref "L2") (pin "1") (pinfunction "1_1") (pintype "passive"))
      (node (ref "U2") (pin "22") (pinfunction "LX1_22") (pintype "power_in"))
    )
    (net (code "95") (name "Net-(U2-LX2)") (class "Default")
      (node (ref "L3") (pin "1") (pinfunction "1_1") (pintype "passive"))
      (node (ref "U2") (pin "1") (pinfunction "LX2_1") (pintype "power_in"))
    )
    (net (code "96") (name "Net-(U2-SW1_OUT)") (class "Default")
      (node (ref "C7") (pin "2") (pinfunction "1_2") (pintype "passive"))
      (node (ref "L2") (pin "2") (pinfunction "2_2") (pintype "passive"))
      (node (ref "R7") (pin "1") (pinfunction "1_1") (pintype "passive"))
      (node (ref "U2") (pin "19") (pinfunction "SW1_OUT_19") (pintype "input"))
    )
    (net (code "97") (name "Net-(U2-SW2_OUT)") (class "Default")
      (node (ref "C9") (pin "2") (pinfunction "1_2") (pintype "passive"))
      (node (ref "L3") (pin "2") (pinfunction "2_2") (pintype "passive"))
      (node (ref "R10") (pin "1") (pinfunction "1_1") (pintype "passive"))
      (node (ref "U2") (pin "3") (pinfunction "SW2_OUT_3") (pintype "input"))
    )
    (net (code "98") (name "Net-(U7-LEDK)") (class "Default")
      (node (ref "R15") (pin "2") (pinfunction "2_2") (pintype "passive"))
      (node (ref "U7") (pin "2") (pinfunction "LEDK_2") (pintype "passive"))
    )
    (net (code "99") (name "VDD_CORE") (class "Default")
      (node (ref "C26") (pin "2") (pinfunction "2_2") (pintype "passive"))
      (node (ref "C27") (pin "2") (pinfunction "2_2") (pintype "passive"))
      (node (ref "C28") (pin "2") (pinfunction "2_2") (pintype "passive"))
      (node (ref "C29") (pin "2") (pinfunction "2_2") (pintype "passive"))
      (node (ref "C30") (pin "2") (pinfunction "2_2") (pintype "passive"))
      (node (ref "C31") (pin "2") (pinfunction "2_2") (pintype "passive"))
      (node (ref "C32") (pin "2") (pinfunction "2_2") (pintype "passive"))
      (node (ref "C33") (pin "2") (pinfunction "2_2") (pintype "passive"))
      (node (ref "C34") (pin "2") (pinfunction "2_2") (pintype "passive"))
      (node (ref "C35") (pin "2") (pinfunction "2_2") (pintype "passive"))
      (node (ref "R7") (pin "2") (pinfunction "2_2") (pintype "passive"))
      (node (ref "U1") (pin "C5") (pinfunction "VDDCORE_C5") (pintype "power_in"))
      (node (ref "U1") (pin "D9") (pinfunction "VDDCORE_D9") (pintype "power_in"))
      (node (ref "U1") (pin "F14") (pinfunction "VDDCORE_F14") (pintype "power_in"))
      (node (ref "U1") (pin "J14") (pinfunction "VDDCORE_J14") (pintype "power_in"))
      (node (ref "U1") (pin "J4") (pinfunction "VDDCORE_J4") (pintype "power_in"))
      (node (ref "U1") (pin "P9") (pinfunction "VDDCORE_P9") (pintype "power_in"))
      (node (ref "U1") (pin "R14") (pinfunction "VDDCORE_R14") (pintype "power_in"))
      (node (ref "U1") (pin "R5") (pinfunction "VDDCORE_R5") (pintype "power_in"))
    )
    (net (code "100") (name "unconnected-(J3-KEY-Pad7)") (class "Default")
      (node (ref "J3") (pin "7") (pinfunction "KEY_7") (pintype "passive+no_connect"))
    )
    (net (code "101") (name "unconnected-(J3-TDI-Pad8)") (class "Default")
      (node (ref "J3") (pin "8") (pinfunction "TDI_8") (pintype "passive+no_connect"))
    )
    (net (code "102") (name "unconnected-(U1D-PIO0_0{slash}FC0_SCK{slash}CTIMER0_MAT0{slash}I2S_BRIDGE_CLK_IN{slash}GPIO_INT_BMAT{slash}SEC_PIO0_0-PadG1)") (class "Default")
      (node (ref "U1") (pin "G1") (pinfunction "PIO0_0/FC0_SCK/CTIMER0_MAT0/I2S_BRIDGE_CLK_IN/GPIO_INT_BMAT/SEC_PIO0_0_G1") (pintype "passive+no_connect"))
    )
    (net (code "103") (name "unconnected-(U1D-PIO0_3{slash}FC0_CTS_SDA_SSEL0{slash}CTIMER0_MAT3{slash}FC1_SSEL2{slash}SEC_PIO0_3-PadH2)") (class "Default")
      (node (ref "U1") (pin "H2") (pinfunction "PIO0_3/FC0_CTS_SDA_SSEL0/CTIMER0_MAT3/FC1_SSEL2/SEC_PIO0_3_H2") (pintype "passive+no_connect"))
    )
    (net (code "104") (name "unconnected-(U1D-PIO0_7{slash}FC1_SCK{slash}SCT0_GPI4{slash}SCT0_OUT4{slash}CTIMER1_MAT0{slash}I2S_BRIDGE_CLK_OUT{slash}SEC_PIO0_7-PadJ2)") (class "Default")
      (node (ref "U1") (pin "J2") (pinfunction "PIO0_7/FC1_SCK/SCT0_GPI4/SCT0_OUT4/CTIMER1_MAT0/I2S_BRIDGE_CLK_OUT/SEC_PIO0_7_J2") (pintype "passive+no_connect"))
    )
    (net (code "105") (name "unconnected-(U1D-PIO0_8{slash}FC1_TXD_SCL_MISO_WS{slash}SCT0_GPI5{slash}SCT0_OUT5{slash}CTIMER1_MAT1{slash}I2S_BRIDGE_WS_OUT{slash}SEC_PIO0_8-PadK4)") (class "Default")
      (node (ref "U1") (pin "K4") (pinfunction "PIO0_8/FC1_TXD_SCL_MISO_WS/SCT0_GPI5/SCT0_OUT5/CTIMER1_MAT1/I2S_BRIDGE_WS_OUT/SEC_PIO0_8_K4") (pintype "passive+no_connect"))
    )
    (net (code "106") (name "unconnected-(U1D-PIO0_9{slash}FC1_RXD_SDA_MOSI_DATA{slash}SCT0_GPI6{slash}SCT0_OUT6{slash}CTIMER1_MAT2{slash}I2S_BRIDGE_DATA_OUT{slash}SEC_PIO0_9-PadL3)") (class "Default")
      (node (ref "U1") (pin "L3") (pinfunction "PIO0_9/FC1_RXD_SDA_MOSI_DATA/SCT0_GPI6/SCT0_OUT6/CTIMER1_MAT2/I2S_BRIDGE_DATA_OUT/SEC_PIO0_9_L3") (pintype "passive+no_connect"))
    )
    (net (code "107") (name "unconnected-(U1D-PIO0_10{slash}FC1_CTS_SDA_SSEL0{slash}SCT0_GPI7{slash}SCT0_OUT7{slash}CTIMER1_MAT3{slash}FC0_SSEL2{slash}SEC_PIO0_10-PadJ3)") (class "Default")
      (node (ref "U1") (pin "J3") (pinfunction "PIO0_10/FC1_CTS_SDA_SSEL0/SCT0_GPI7/SCT0_OUT7/CTIMER1_MAT3/FC0_SSEL2/SEC_PIO0_10_J3") (pintype "passive+no_connect"))
    )
    (net (code "108") (name "unconnected-(U1D-PIO0_13{slash}FC1_SSEL3{slash}SCT0_GPI3{slash}SCT0_OUT3{slash}CTIMER0_MAT1{slash}SEC_PIO0_13{slash}ADC0_9-PadG3)") (class "Default")
      (node (ref "U1") (pin "G3") (pinfunction "PIO0_13/FC1_SSEL3/SCT0_GPI3/SCT0_OUT3/CTIMER0_MAT1/SEC_PIO0_13/ADC0_9_G3") (pintype "passive+no_connect"))
    )
    (net (code "109") (name "unconnected-(U1D-PIO1_24{slash}FLEXSPI0A_DATA4{slash}SCT0_GPI3-PadT7)") (class "Default")
      (node (ref "U1") (pin "T7") (pinfunction "PIO1_24/FLEXSPI0A_DATA4/SCT0_GPI3_T7") (pintype "passive+no_connect"))
    )
    (net (code "110") (name "unconnected-(U1D-PIO1_25{slash}FLEXSPI0A_DATA5{slash}SCT0_OUT3-PadU7)") (class "Default")
      (node (ref "U1") (pin "U7") (pinfunction "PIO1_25/FLEXSPI0A_DATA5/SCT0_OUT3_U7") (pintype "passive+no_connect"))
    )
    (net (code "111") (name "unconnected-(U1D-PIO1_26{slash}FLEXSPI0A_DATA6{slash}SCT0_GPI4-PadR7)") (class "Default")
      (node (ref "U1") (pin "R7") (pinfunction "PIO1_26/FLEXSPI0A_DATA6/SCT0_GPI4_R7") (pintype "passive+no_connect"))
    )
    (net (code "112") (name "unconnected-(U1D-PIO1_27{slash}FLEXSPI0A_DATA7{slash}SCT0_OUT4-PadT8)") (class "Default")
      (node (ref "U1") (pin "T8") (pinfunction "PIO1_27/FLEXSPI0A_DATA7/SCT0_OUT4_T8") (pintype "passive+no_connect"))
    )
    (net (code "113") (name "unconnected-(U1D-PIO1_28{slash}FLEXSPI0A_DQS{slash}SCT0_GPI5-PadU9)") (class "Default")
      (node (ref "U1") (pin "U9") (pinfunction "PIO1_28/FLEXSPI0A_DQS/SCT0_GPI5_U9") (pintype "passive+no_connect"))
    )
    (net (code "114") (name "unconnected-(U1D-PIO1_29{slash}FLEXSPI0A_SS1_N{slash}SCT0_OUT5{slash}UTICK_CAP2{slash}CTIMER_INP13{slash}FLEXSPI0B_SCLK-PadU3)") (class "Default")
      (node (ref "U1") (pin "U3") (pinfunction "PIO1_29/FLEXSPI0A_SS1_N/SCT0_OUT5/UTICK_CAP2/CTIMER_INP13/FLEXSPI0B_SCLK_U3") (pintype "passive+no_connect"))
    )
    (net (code "115") (name "unconnected-(U1D-PIO2_12{slash}SCT0_OUT6{slash}CTIMER2_MAT2-PadT3)") (class "Default")
      (node (ref "U1") (pin "T3") (pinfunction "PIO2_12/SCT0_OUT6/CTIMER2_MAT2_T3") (pintype "passive+no_connect"))
    )
    (net (code "116") (name "unconnected-(U1D-PIO2_13{slash}SCT0_OUT7{slash}CTIMER2_MAT3{slash}CMP0_OUT-PadT1)") (class "Default")
      (node (ref "U1") (pin "T1") (pinfunction "PIO2_13/SCT0_OUT7/CTIMER2_MAT3/CMP0_OUT_T1") (pintype "passive+no_connect"))
    )
    (net (code "117") (name "unconnected-(U1D-PIO2_15{slash}SCT0_OUT9{slash}CLKIN{slash}CMP0_D-PadE2)") (class "Default")
      (node (ref "U1") (pin "E2") (pinfunction "PIO2_15/SCT0_OUT9/CLKIN/CMP0_D_E2") (pintype "passive+no_connect"))
    )
    (net (code "118") (name "unconnected-(U1E-PIO0_17{slash}FC2_CTS_SDA_SSEL0{slash}SCT0_GPI3{slash}SCT0_OUT3{slash}CTIMER2_MAT3{slash}FC5_SSEL2{slash}SEC_PIO0_17-PadD7)") (class "Default")
      (node (ref "U1") (pin "D7") (pinfunction "PIO0_17/FC2_CTS_SDA_SSEL0/SCT0_GPI3/SCT0_OUT3/CTIMER2_MAT3/FC5_SSEL2/SEC_PIO0_17_D7") (pintype "passive+no_connect"))
    )
    (net (code "119") (name "unconnected-(U1E-PIO0_18{slash}FC2_RTS_SCL_SSEL1{slash}SCT0_GPI6{slash}SCT0_OUT6{slash}CTIMER_INP4{slash}FC5_SSEL3{slash}SEC_PIO0_18-PadB7)") (class "Default")
      (node (ref "U1") (pin "B7") (pinfunction "PIO0_18/FC2_RTS_SCL_SSEL1/SCT0_GPI6/SCT0_OUT6/CTIMER_INP4/FC5_SSEL3/SEC_PIO0_18_B7") (pintype "passive+no_connect"))
    )
    (net (code "120") (name "unconnected-(U1E-PIO0_20{slash}FC2_SSEL3{slash}SCT0_GPI5{slash}SCT0_OUT5{slash}CTIMER0_MAT2{slash}CTIMER_INP11{slash}SEC_PIO0_20{slash}ADC0_10-PadB2)") (class "Default")
      (node (ref "U1") (pin "B2") (pinfunction "PIO0_20/FC2_SSEL3/SCT0_GPI5/SCT0_OUT5/CTIMER0_MAT2/CTIMER_INP11/SEC_PIO0_20/ADC0_10_B2") (pintype "passive+no_connect"))
    )
    (net (code "121") (name "unconnected-(U1E-PIO0_24{slash}FC3_CTS_SDA_SSEL0{slash}CTIMER3_MAT3{slash}FC2_SSEL2{slash}TRACEDATA(2){slash}CLKOUT{slash}SEC_PIO0_24-PadB9)") (class "Default")
      (node (ref "U1") (pin "B9") (pinfunction "PIO0_24/FC3_CTS_SDA_SSEL0/CTIMER3_MAT3/FC2_SSEL2/TRACEDATA(2)/CLKOUT/SEC_PIO0_24_B9") (pintype "passive+no_connect"))
    )
    (net (code "122") (name "unconnected-(U1E-PIO0_25{slash}FC3_RTS_SCL_SSEL1{slash}FREQME_GPIO_CLK{slash}CTIMER_INP6{slash}FC2_SSEL3{slash}TRACEDATA(3){slash}CLKIN{slash}SEC_PIO0_25-PadA9)") (class "Default")
      (node (ref "U1") (pin "A9") (pinfunction "PIO0_25/FC3_RTS_SCL_SSEL1/FREQME_GPIO_CLK/CTIMER_INP6/FC2_SSEL3/TRACEDATA(3)/CLKIN/SEC_PIO0_25_A9") (pintype "passive+no_connect"))
    )
    (net (code "123") (name "unconnected-(U1E-PIO0_27{slash}FC3_SSEL3{slash}SCT0_GPI7{slash}SCT0_OUT7{slash}CTIMER0_MAT3{slash}SEC_PIO0_27{slash}ADC0_11-PadB3)") (class "Default")
      (node (ref "U1") (pin "B3") (pinfunction "PIO0_27/FC3_SSEL3/SCT0_GPI7/SCT0_OUT7/CTIMER0_MAT3/SEC_PIO0_27/ADC0_11_B3") (pintype "passive+no_connect"))
    )
    (net (code "124") (name "unconnected-(U1E-PIO0_31{slash}FC4_CTS_SDA_SSEL0{slash}SCT0_GPI0{slash}SCT0_OUT6{slash}CTIMER4_MAT3{slash}FC3_SSEL2{slash}SEC_PIO0_31-PadA11)") (class "Default")
      (node (ref "U1") (pin "A11") (pinfunction "PIO0_31/FC4_CTS_SDA_SSEL0/SCT0_GPI0/SCT0_OUT6/CTIMER4_MAT3/FC3_SSEL2/SEC_PIO0_31_A11") (pintype "passive+no_connect"))
    )
    (net (code "125") (name "unconnected-(U1E-PIO1_0{slash}FC4_RTS_SCL_SSEL1{slash}SCT0_GPI1{slash}SCT0_OUT7{slash}CTIMER_INP8{slash}FC3_SSEL3-PadE17)") (class "Default")
      (node (ref "U1") (pin "E17") (pinfunction "PIO1_0/FC4_RTS_SCL_SSEL1/SCT0_GPI1/SCT0_OUT7/CTIMER_INP8/FC3_SSEL3_E17") (pintype "passive+no_connect"))
    )
    (net (code "126") (name "unconnected-(U1E-PIO1_1{slash}FC4_SSEL2{slash}SCT0_GPI2{slash}SCT0_OUT8{slash}CTIMER1_MAT0-PadG15)") (class "Default")
      (node (ref "U1") (pin "G15") (pinfunction "PIO1_1/FC4_SSEL2/SCT0_GPI2/SCT0_OUT8/CTIMER1_MAT0_G15") (pintype "passive+no_connect"))
    )
    (net (code "127") (name "unconnected-(U1E-PIO1_2{slash}FC4_SSEL3{slash}SCT0_GPI3{slash}SCT0_OUT9{slash}CTIMER1_MAT1{slash}CMP0_C-PadA7)") (class "Default")
      (node (ref "U1") (pin "A7") (pinfunction "PIO1_2/FC4_SSEL3/SCT0_GPI3/SCT0_OUT9/CTIMER1_MAT1/CMP0_C_A7") (pintype "passive+no_connect"))
    )
    (net (code "128") (name "unconnected-(U1E-PIO1_7{slash}FC5_RTS_SCL_SSEL1{slash}SCT0_GPI5{slash}SCT0_OUT5{slash}CTIMER_INP9{slash}FC4_SSEL3-PadJ15)") (class "Default")
      (node (ref "U1") (pin "J15") (pinfunction "PIO1_7/FC5_RTS_SCL_SSEL1/SCT0_GPI5/SCT0_OUT5/CTIMER_INP9/FC4_SSEL3_J15") (pintype "passive+no_connect"))
    )
    (net (code "129") (name "unconnected-(U1E-PIO2_27{slash}USB1_OVERCURRENTN-PadM14)") (class "Default")
      (node (ref "U1") (pin "M14") (pinfunction "PIO2_27/USB1_OVERCURRENTN_M14") (pintype "passive+no_connect"))
    )
    (net (code "130") (name "unconnected-(U1E-PIO2_28{slash}USB1_PORTPWRN-PadN15)") (class "Default")
      (node (ref "U1") (pin "N15") (pinfunction "PIO2_28/USB1_PORTPWRN_N15") (pintype "passive+no_connect"))
    )
    (net (code "131") (name "unconnected-(U1F-PIO2_4{slash}SD0_WR_PRT{slash}SCT0_OUT2{slash}SD0_DS-PadT13)") (class "Default")
      (node (ref "U1") (pin "T13") (pinfunction "PIO2_4/SD0_WR_PRT/SCT0_OUT2/SD0_DS_T13") (pintype "passive+no_connect"))
    )
    (net (code "132") (name "unconnected-(U1F-PIO2_11{slash}SD0_VOLT{slash}SCT0_GPI7{slash}CTIMER2_MAT1-PadT16)") (class "Default")
      (node (ref "U1") (pin "T16") (pinfunction "PIO2_11/SD0_VOLT/SCT0_GPI7/CTIMER2_MAT1_T16") (pintype "passive+no_connect"))
    )
    (net (code "133") (name "unconnected-(U1H-RTCXIN-PadB17)") (class "Default")
      (node (ref "U1") (pin "B17") (pinfunction "RTCXIN_B17") (pintype "input+no_connect"))
    )
    (net (code "134") (name "unconnected-(U1H-RTCXOUT-PadA17)") (class "Default")
      (node (ref "U1") (pin "A17") (pinfunction "RTCXOUT_A17") (pintype "output+no_connect"))
    )
  )
)
